# keyboard_main.net
KiCad netlist of a schematic drawn in Altium Designer
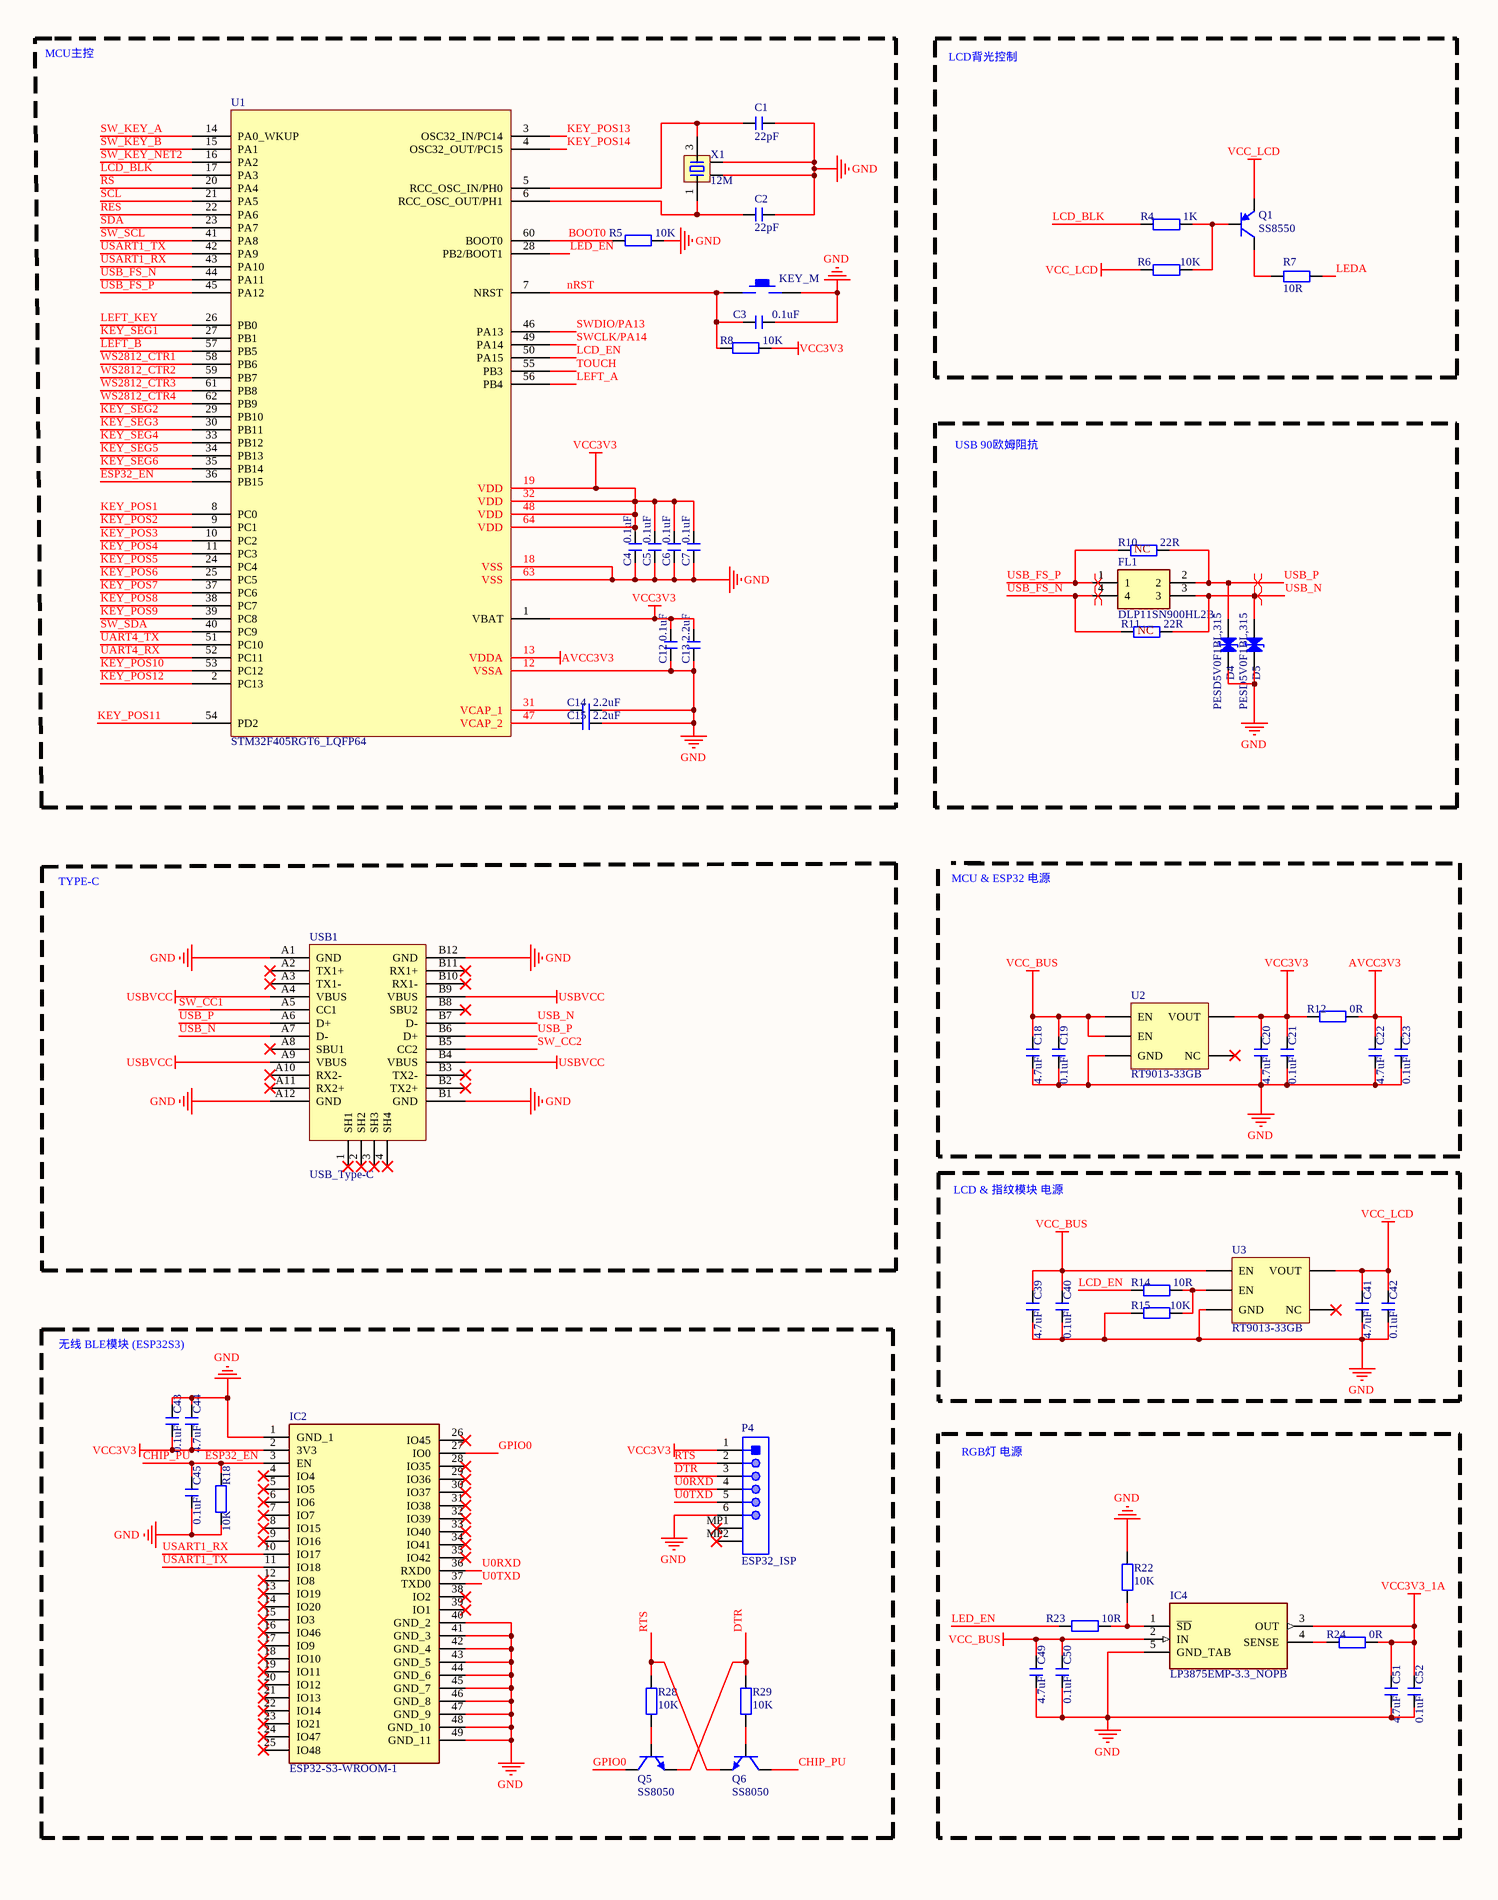
[diagram p0: keyboard_main.SchDoc, left]
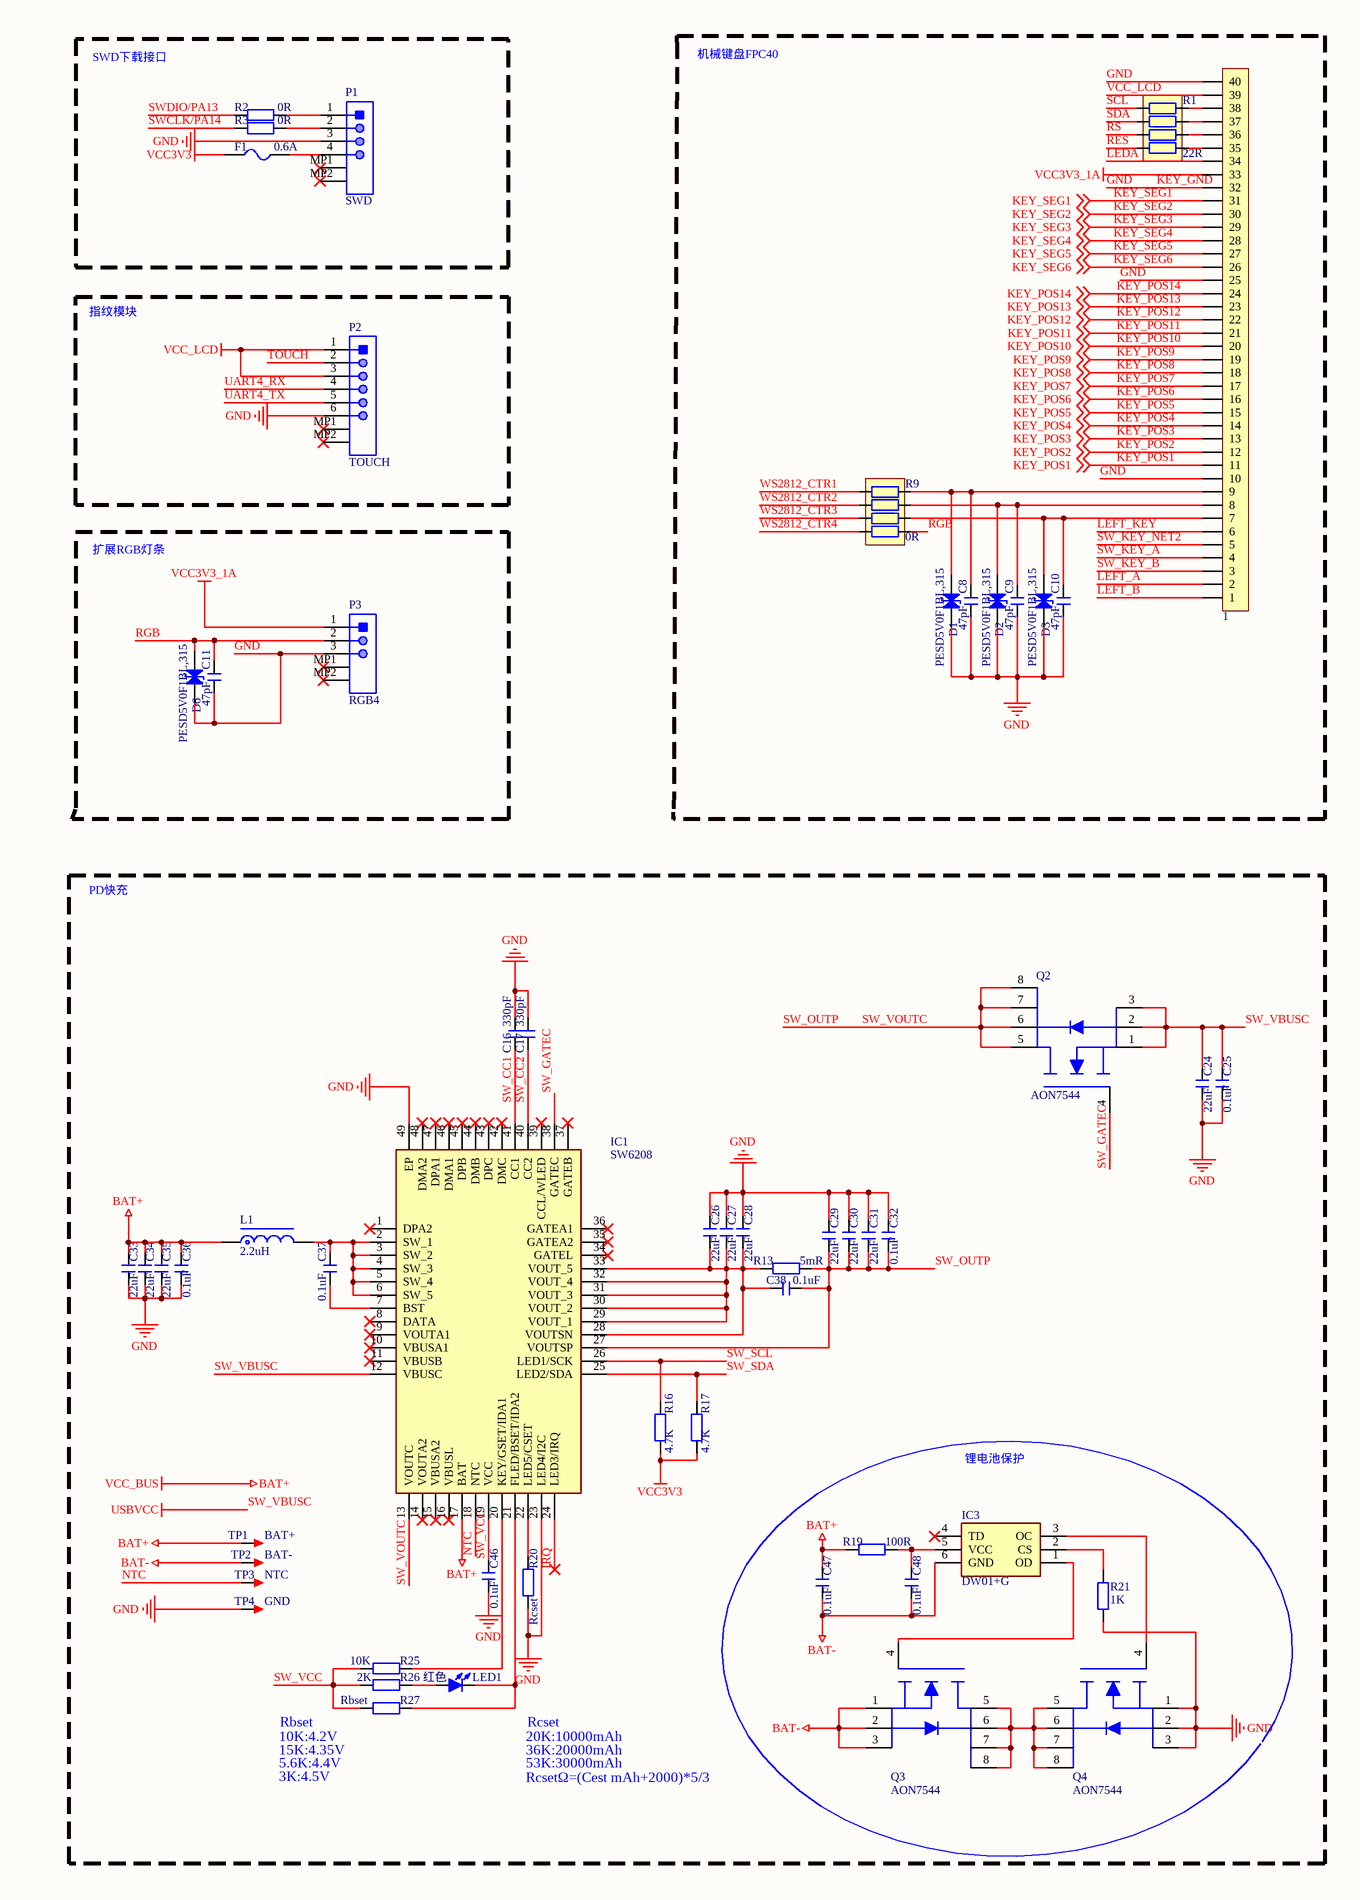
[diagram p1: keyboard_main.SchDoc, right]

(export (version "E")
  (design (tool "Eeschema 10.0.6"))
  (components
    (comp (ref "1")
      (value "FPC1.0-40P")
      (footprint "FPC0.5 2H-WS-40P")
      (description "FPC连接器")
      (fields (field (name "版权归属") "黎明电子style"))
      (libsource (lib "FPC连接器") (part "FPC-40P"))
    )
    (comp (ref "C1")
      (value "22pF")
      (footprint "C 0402_L")
      (description "贴片电容")
      (libsource (lib "0.1 - 电阻-电容-电感") (part "C"))
    )
    (comp (ref "C2")
      (value "22pF")
      (footprint "C 0402_L")
      (description "贴片电容")
      (libsource (lib "0.1 - 电阻-电容-电感") (part "C"))
    )
    (comp (ref "C3")
      (value "0.1uF")
      (footprint "C 0402_L")
      (description "贴片电容")
      (libsource (lib "0.1 - 电阻-电容-电感") (part "C"))
    )
    (comp (ref "C4")
      (value "0.1uF")
      (footprint "C 0402_L")
      (description "贴片电容")
      (libsource (lib "0.1 - 电阻-电容-电感") (part "C"))
    )
    (comp (ref "C5")
      (value "0.1uF")
      (footprint "C 0402_L")
      (description "贴片电容")
      (libsource (lib "0.1 - 电阻-电容-电感") (part "C"))
    )
    (comp (ref "C6")
      (value "0.1uF")
      (footprint "C 0402_L")
      (description "贴片电容")
      (libsource (lib "0.1 - 电阻-电容-电感") (part "C"))
    )
    (comp (ref "C7")
      (value "0.1uF")
      (footprint "C 0402_L")
      (description "贴片电容")
      (libsource (lib "0.1 - 电阻-电容-电感") (part "C"))
    )
    (comp (ref "C8")
      (value "47pF")
      (footprint "C 0402_L")
      (description "贴片电容")
      (libsource (lib "0.1 - 电阻-电容-电感") (part "C"))
    )
    (comp (ref "C9")
      (value "47pF")
      (footprint "C 0402_L")
      (description "贴片电容")
      (libsource (lib "0.1 - 电阻-电容-电感") (part "C"))
    )
    (comp (ref "C10")
      (value "47pF")
      (footprint "C 0402_L")
      (description "贴片电容")
      (libsource (lib "0.1 - 电阻-电容-电感") (part "C"))
    )
    (comp (ref "C11")
      (value "47pF")
      (footprint "C 0402_L")
      (description "贴片电容")
      (libsource (lib "0.1 - 电阻-电容-电感") (part "C"))
    )
    (comp (ref "C12")
      (value "0.1uF")
      (footprint "C 0402_L")
      (description "贴片电容")
      (libsource (lib "0.1 - 电阻-电容-电感") (part "C"))
    )
    (comp (ref "C13")
      (value "2.2uF")
      (footprint "C 0402_L")
      (description "贴片电容")
      (libsource (lib "0.1 - 电阻-电容-电感") (part "C"))
    )
    (comp (ref "C14")
      (value "2.2uF")
      (footprint "C 0402_L")
      (description "贴片电容")
      (libsource (lib "0.1 - 电阻-电容-电感") (part "C"))
    )
    (comp (ref "C15")
      (value "2.2uF")
      (footprint "C 0402_L")
      (description "贴片电容")
      (libsource (lib "0.1 - 电阻-电容-电感") (part "C"))
    )
    (comp (ref "C16")
      (value "330pF")
      (footprint "C 0402_L")
      (description "贴片电容")
      (libsource (lib "0.1 - 电阻-电容-电感") (part "C"))
    )
    (comp (ref "C17")
      (value "330pF")
      (footprint "C 0402_L")
      (description "贴片电容")
      (libsource (lib "0.1 - 电阻-电容-电感") (part "C"))
    )
    (comp (ref "C18")
      (value "4.7uF")
      (footprint "C 0402_L")
      (description "贴片电容")
      (libsource (lib "0.1 - 电阻-电容-电感") (part "C"))
    )
    (comp (ref "C19")
      (value "0.1uF")
      (footprint "C 0402_L")
      (description "贴片电容")
      (libsource (lib "0.1 - 电阻-电容-电感") (part "C"))
    )
    (comp (ref "C20")
      (value "4.7uF")
      (footprint "C 0402_L")
      (description "贴片电容")
      (libsource (lib "0.1 - 电阻-电容-电感") (part "C"))
    )
    (comp (ref "C21")
      (value "0.1uF")
      (footprint "C 0402_L")
      (description "贴片电容")
      (libsource (lib "0.1 - 电阻-电容-电感") (part "C"))
    )
    (comp (ref "C22")
      (value "4.7uF")
      (footprint "C 0402_L")
      (description "贴片电容")
      (libsource (lib "0.1 - 电阻-电容-电感") (part "C"))
    )
    (comp (ref "C23")
      (value "0.1uF")
      (footprint "C 0402_L")
      (description "贴片电容")
      (libsource (lib "0.1 - 电阻-电容-电感") (part "C"))
    )
    (comp (ref "C24")
      (value "22uF")
      (footprint "C 0805_L")
      (description "贴片电容")
      (libsource (lib "0.1 - 电阻-电容-电感") (part "C"))
    )
    (comp (ref "C25")
      (value "0.1uF")
      (footprint "C 0805_L")
      (description "贴片电容")
      (libsource (lib "0.1 - 电阻-电容-电感") (part "C"))
    )
    (comp (ref "C26")
      (value "22uF")
      (footprint "C 0805_L")
      (description "贴片电容")
      (libsource (lib "0.1 - 电阻-电容-电感") (part "C"))
    )
    (comp (ref "C27")
      (value "22uF")
      (footprint "C 0805_L")
      (description "贴片电容")
      (libsource (lib "0.1 - 电阻-电容-电感") (part "C"))
    )
    (comp (ref "C28")
      (value "22uF")
      (footprint "C 0805_L")
      (description "贴片电容")
      (libsource (lib "0.1 - 电阻-电容-电感") (part "C"))
    )
    (comp (ref "C29")
      (value "22uF")
      (footprint "C 0805_L")
      (description "贴片电容")
      (libsource (lib "0.1 - 电阻-电容-电感") (part "C"))
    )
    (comp (ref "C30")
      (value "22uF")
      (footprint "C 0805_L")
      (description "贴片电容")
      (libsource (lib "0.1 - 电阻-电容-电感") (part "C"))
    )
    (comp (ref "C31")
      (value "22uF")
      (footprint "C 0805_L")
      (description "贴片电容")
      (libsource (lib "0.1 - 电阻-电容-电感") (part "C"))
    )
    (comp (ref "C32")
      (value "0.1uF")
      (footprint "C 0805_L")
      (description "贴片电容")
      (libsource (lib "0.1 - 电阻-电容-电感") (part "C"))
    )
    (comp (ref "C33")
      (value "22uF")
      (footprint "C 0805_L")
      (description "贴片电容")
      (libsource (lib "0.1 - 电阻-电容-电感") (part "C"))
    )
    (comp (ref "C34")
      (value "22uF")
      (footprint "C 0805_L")
      (description "贴片电容")
      (libsource (lib "0.1 - 电阻-电容-电感") (part "C"))
    )
    (comp (ref "C35")
      (value "22uF")
      (footprint "C 0805_L")
      (description "贴片电容")
      (libsource (lib "0.1 - 电阻-电容-电感") (part "C"))
    )
    (comp (ref "C36")
      (value "0.1uF")
      (footprint "C 0805_L")
      (description "贴片电容")
      (libsource (lib "0.1 - 电阻-电容-电感") (part "C"))
    )
    (comp (ref "C37")
      (value "0.1uF")
      (footprint "C 0805_L")
      (description "贴片电容")
      (libsource (lib "0.1 - 电阻-电容-电感") (part "C"))
    )
    (comp (ref "C38")
      (value "0.1uF")
      (footprint "C 0805_L")
      (description "贴片电容")
      (libsource (lib "0.1 - 电阻-电容-电感") (part "C"))
    )
    (comp (ref "C39")
      (value "4.7uF")
      (footprint "C 0402_L")
      (description "贴片电容")
      (libsource (lib "0.1 - 电阻-电容-电感") (part "C"))
    )
    (comp (ref "C40")
      (value "0.1uF")
      (footprint "C 0402_L")
      (description "贴片电容")
      (libsource (lib "0.1 - 电阻-电容-电感") (part "C"))
    )
    (comp (ref "C41")
      (value "4.7uF")
      (footprint "C 0402_L")
      (description "贴片电容")
      (libsource (lib "0.1 - 电阻-电容-电感") (part "C"))
    )
    (comp (ref "C42")
      (value "0.1uF")
      (footprint "C 0402_L")
      (description "贴片电容")
      (libsource (lib "0.1 - 电阻-电容-电感") (part "C"))
    )
    (comp (ref "C43")
      (value "0.1uF")
      (footprint "C 0402_L")
      (description "贴片电容")
      (libsource (lib "0.1 - 电阻-电容-电感") (part "C"))
    )
    (comp (ref "C44")
      (value "4.7uF")
      (footprint "C 0402_L")
      (description "贴片电容")
      (libsource (lib "0.1 - 电阻-电容-电感") (part "C"))
    )
    (comp (ref "C45")
      (value "0.1uF")
      (footprint "C 0402_L")
      (description "贴片电容")
      (libsource (lib "0.1 - 电阻-电容-电感") (part "C"))
    )
    (comp (ref "C46")
      (value "0.1uF")
      (footprint "C 0402_L")
      (description "贴片电容")
      (libsource (lib "0.1 - 电阻-电容-电感") (part "C"))
    )
    (comp (ref "C47")
      (value "0.1uF")
      (footprint "C 0805_L")
      (description "贴片电容")
      (libsource (lib "0.1 - 电阻-电容-电感") (part "C"))
    )
    (comp (ref "C48")
      (value "0.1uF")
      (footprint "C 0805_L")
      (description "贴片电容")
      (libsource (lib "0.1 - 电阻-电容-电感") (part "C"))
    )
    (comp (ref "C49")
      (value "4.7uF")
      (footprint "C 0402_L")
      (description "贴片电容")
      (libsource (lib "0.1 - 电阻-电容-电感") (part "C"))
    )
    (comp (ref "C50")
      (value "0.1uF")
      (footprint "C 0402_L")
      (description "贴片电容")
      (libsource (lib "0.1 - 电阻-电容-电感") (part "C"))
    )
    (comp (ref "C51")
      (value "4.7uF")
      (footprint "C 0402_L")
      (description "贴片电容")
      (libsource (lib "0.1 - 电阻-电容-电感") (part "C"))
    )
    (comp (ref "C52")
      (value "0.1uF")
      (footprint "C 0402_L")
      (description "贴片电容")
      (libsource (lib "0.1 - 电阻-电容-电感") (part "C"))
    )
    (comp (ref "D1")
      (value "PESD5V0F1BL,315")
      (footprint "SOD-882_L1.0-W0.6-BI")
      (description "PESD5V0F1BL,315、ESD二极管、5.5V")
      (libsource (lib "0.2 -  二极管-整流桥") (part "PESD5V0F1BL,315"))
    )
    (comp (ref "D2")
      (value "PESD5V0F1BL,315")
      (footprint "SOD-882_L1.0-W0.6-BI")
      (description "PESD5V0F1BL,315、ESD二极管、5.5V")
      (libsource (lib "0.2 -  二极管-整流桥") (part "PESD5V0F1BL,315"))
    )
    (comp (ref "D3")
      (value "PESD5V0F1BL,315")
      (footprint "SOD-882_L1.0-W0.6-BI")
      (description "PESD5V0F1BL,315、ESD二极管、5.5V")
      (libsource (lib "0.2 -  二极管-整流桥") (part "PESD5V0F1BL,315"))
    )
    (comp (ref "D4")
      (value "PESD5V0F1BL,315")
      (footprint "SOD-882_L1.0-W0.6-BI")
      (description "PESD5V0F1BL,315、ESD二极管、5.5V")
      (libsource (lib "0.2 -  二极管-整流桥") (part "PESD5V0F1BL,315"))
    )
    (comp (ref "D5")
      (value "PESD5V0F1BL,315")
      (footprint "SOD-882_L1.0-W0.6-BI")
      (description "PESD5V0F1BL,315、ESD二极管、5.5V")
      (libsource (lib "0.2 -  二极管-整流桥") (part "PESD5V0F1BL,315"))
    )
    (comp (ref "D6")
      (value "PESD5V0F1BL,315")
      (footprint "SOD-882_L1.0-W0.6-BI")
      (description "PESD5V0F1BL,315、ESD二极管、5.5V")
      (libsource (lib "0.2 -  二极管-整流桥") (part "PESD5V0F1BL,315"))
    )
    (comp (ref "F1")
      (value "0.6A")
      (footprint "FU 0402")
      (description "贴片保险丝")
      (libsource (lib "2.0 - 保险丝-晶振-光耦") (part "FU"))
    )
    (comp (ref "FL1")
      (value "DLP11SN900HL2B")
      (footprint "vSeasky:DLP11SA350HL2B")
      (description "Filter")
      (fields (field (name "MOUSER PART NUMBER") "81-DLP11SN900HL2B"))
      (libsource (lib "vSeasky") (part "DLP11SN900HL2B"))
    )
    (comp (ref "IC1")
      (value "SW6208")
      (footprint "vSeasky:QFN40P600X600X80-49N")
      (description "Integrated Circuit")
      (libsource (lib "*") (part "SW6208"))
    )
    (comp (ref "IC2")
      (value "ESP32-S3-WROOM-1")
      (footprint "mx_pcb_library:ESP32S3WROOM1")
      (description "Integrated Circuit")
      (libsource (lib "mx_pcb_library") (part "ESP32-S3-WROOM-1"))
    )
    (comp (ref "IC3")
      (value "DW01+G")
      (footprint "vSeasky:SOT95P280X145-6N")
      (description "Integrated Circuit")
      (libsource (lib "*") (part "DW01+G"))
    )
    (comp (ref "IC4")
      (value "LP3875EMP-3.3_NOPB")
      (footprint "mx_pcb_library:SOT150P700X180-5N")
      (description "Integrated Circuit")
      (fields
        (field (name "MANUFACTURER_PART_NUMBER") "LP3875EMP-3.3/NOPB")
        (field (name "MOUSER PART NUMBER") "926-LP3875EMP33NOPB")
      )
      (libsource (lib "mx_pcb_library") (part "LP3875EMP-3.3_NOPB"))
    )
    (comp (ref "L1")
      (value "2.2uH")
      (footprint "CD42")
      (description "CD系列贴片线绕功率电感")
      (libsource (lib "0.1 - 电阻-电容-电感") (part "L-SMD"))
    )
    (comp (ref "LED1")
      (value "红色")
      (footprint "LED 0805G")
      (description "贴片LED")
      (libsource (lib "0.3 - LED发光二极管") (part "LED-SMD"))
    )
    (comp (ref "P1")
      (value "SWD")
      (footprint "JST-SM04B-SRSS-TB_V")
      (description "Male Header, Pitch 1 mm, 1 x 4 Position, Height 2.9 mm, -25 to 85 degC, RoHS, Tape and Reel")
      (fields (field (name "MANUFACTURER") "JST"))
      (libsource (lib "JST SH Connector") (part "SM04B-SRSS-TB(LF)(SN)"))
    )
    (comp (ref "P2")
      (value "TOUCH")
      (footprint "JST-SM06B-SRSS-TB_V")
      (description "Male Header, Pitch 1 mm, 1 x 6 Position, Height 2.9 mm, -25 to 85 degC, RoHS, Tape and Reel")
      (fields (field (name "MANUFACTURER") "JST"))
      (libsource (lib "JST SH Connector") (part "SM06B-SRSS-TB(LF)(SN)"))
    )
    (comp (ref "P3")
      (value "RGB4")
      (footprint "JST-SM03B-SRSS-TB_V")
      (description "Male Header, Pitch 1 mm, 1 x 3 Position, Height 2.9 mm, -25 to 85 degC, RoHS, Tape and Reel")
      (fields (field (name "MANUFACTURER") "JST"))
      (libsource (lib "JST SH Connector") (part "SM03B-SRSS-TB(LF)(SN)"))
    )
    (comp (ref "P4")
      (value "ESP32_ISP")
      (footprint "JST-SM06B-SRSS-TB_V")
      (description "Male Header, Pitch 1 mm, 1 x 6 Position, Height 2.9 mm, -25 to 85 degC, RoHS, Tape and Reel")
      (fields (field (name "MANUFACTURER") "JST"))
      (libsource (lib "JST SH Connector") (part "SM06B-SRSS-TB(LF)(SN)"))
    )
    (comp (ref "Q1")
      (value "SS8550")
      (footprint "SOT23-3N")
      (description "高频放大-PNP型")
      (libsource (lib "0.4 - 三极管") (part "8550-SMD"))
    )
    (comp (ref "Q2")
      (value "AON7544")
      (footprint "DFN-8_L3.0-W3.0-P0.65-BL")
      (libsource (lib "mx_pcb_library") (part "BSC070N10NS3GATMA1"))
    )
    (comp (ref "Q3")
      (value "AON7544")
      (footprint "DFN-8_L3.0-W3.0-P0.65-BL")
      (libsource (lib "mx_pcb_library") (part "BSC070N10NS3GATMA1"))
    )
    (comp (ref "Q4")
      (value "AON7544")
      (footprint "DFN-8_L3.0-W3.0-P0.65-BL")
      (libsource (lib "mx_pcb_library") (part "BSC070N10NS3GATMA1"))
    )
    (comp (ref "Q5")
      (value "SS8050")
      (footprint "SOT23-3N")
      (description "高频放大-NPN型")
      (libsource (lib "0.4 - 三极管") (part "8050-SMD"))
    )
    (comp (ref "Q6")
      (value "SS8050")
      (footprint "SOT23-3N")
      (description "高频放大-NPN型")
      (libsource (lib "0.4 - 三极管") (part "8050-SMD"))
    )
    (comp (ref "R1")
      (value "22R")
      (footprint "RCA-8P4R-0402")
      (description "贴片排阻")
      (libsource (lib "0.1 - 电阻-电容-电感") (part "R-8P4R"))
    )
    (comp (ref "R2")
      (value "0R")
      (footprint "R 0402_L")
      (description "贴片电阻")
      (libsource (lib "0.1 - 电阻-电容-电感") (part "R"))
    )
    (comp (ref "R3")
      (value "0R")
      (footprint "R 0402_L")
      (description "贴片电阻")
      (libsource (lib "0.1 - 电阻-电容-电感") (part "R"))
    )
    (comp (ref "R4")
      (value "1K")
      (footprint "R 0402_L")
      (description "贴片电阻")
      (libsource (lib "0.1 - 电阻-电容-电感") (part "R"))
    )
    (comp (ref "R5")
      (value "10K")
      (footprint "R 0402_L")
      (description "贴片电阻")
      (libsource (lib "0.1 - 电阻-电容-电感") (part "R"))
    )
    (comp (ref "R6")
      (value "10K")
      (footprint "R 0402_L")
      (description "贴片电阻")
      (libsource (lib "0.1 - 电阻-电容-电感") (part "R"))
    )
    (comp (ref "R7")
      (value "10R")
      (footprint "R 0402_L")
      (description "贴片电阻")
      (libsource (lib "0.1 - 电阻-电容-电感") (part "R"))
    )
    (comp (ref "R8")
      (value "10K")
      (footprint "R 0402_L")
      (description "贴片电阻")
      (libsource (lib "0.1 - 电阻-电容-电感") (part "R"))
    )
    (comp (ref "R9")
      (value "0R")
      (footprint "RCA-8P4R-0402")
      (description "贴片排阻")
      (libsource (lib "0.1 - 电阻-电容-电感") (part "R-8P4R"))
    )
    (comp (ref "R10")
      (value "22R")
      (footprint "R 0402_L")
      (description "贴片电阻")
      (libsource (lib "0.1 - 电阻-电容-电感") (part "R"))
    )
    (comp (ref "R11")
      (value "22R")
      (footprint "R 0402_L")
      (description "贴片电阻")
      (libsource (lib "0.1 - 电阻-电容-电感") (part "R"))
    )
    (comp (ref "R12")
      (value "0R")
      (footprint "R 0402_L")
      (description "贴片电阻")
      (libsource (lib "0.1 - 电阻-电容-电感") (part "R"))
    )
    (comp (ref "R13")
      (value "5mR")
      (footprint "R 1206_L")
      (description "贴片电阻")
      (libsource (lib "0.1 - 电阻-电容-电感") (part "R"))
    )
    (comp (ref "R14")
      (value "10R")
      (footprint "R 0402_L")
      (description "贴片电阻")
      (libsource (lib "0.1 - 电阻-电容-电感") (part "R"))
    )
    (comp (ref "R15")
      (value "10K")
      (footprint "R 0402_L")
      (description "贴片电阻")
      (libsource (lib "0.1 - 电阻-电容-电感") (part "R"))
    )
    (comp (ref "R16")
      (value "4.7K")
      (footprint "R 0402_L")
      (description "贴片电阻")
      (libsource (lib "0.1 - 电阻-电容-电感") (part "R"))
    )
    (comp (ref "R17")
      (value "4.7K")
      (footprint "R 0402_L")
      (description "贴片电阻")
      (libsource (lib "0.1 - 电阻-电容-电感") (part "R"))
    )
    (comp (ref "R18")
      (value "10K")
      (footprint "R 0402_L")
      (description "贴片电阻")
      (libsource (lib "0.1 - 电阻-电容-电感") (part "R"))
    )
    (comp (ref "R19")
      (value "100R")
      (footprint "R 0402_L")
      (description "贴片电阻")
      (libsource (lib "0.1 - 电阻-电容-电感") (part "R"))
    )
    (comp (ref "R20")
      (value "Rcset")
      (footprint "R 0402_L")
      (description "贴片电阻")
      (libsource (lib "0.1 - 电阻-电容-电感") (part "R"))
    )
    (comp (ref "R21")
      (value "1K")
      (footprint "R 0402_L")
      (description "贴片电阻")
      (libsource (lib "0.1 - 电阻-电容-电感") (part "R"))
    )
    (comp (ref "R22")
      (value "10K")
      (footprint "R 0402_L")
      (description "贴片电阻")
      (libsource (lib "0.1 - 电阻-电容-电感") (part "R"))
    )
    (comp (ref "R23")
      (value "10R")
      (footprint "R 0402_L")
      (description "贴片电阻")
      (libsource (lib "0.1 - 电阻-电容-电感") (part "R"))
    )
    (comp (ref "R24")
      (value "0R")
      (footprint "R 0402_L")
      (description "贴片电阻")
      (libsource (lib "0.1 - 电阻-电容-电感") (part "R"))
    )
    (comp (ref "R25")
      (value "10K")
      (footprint "R 0402_L")
      (description "贴片电阻")
      (libsource (lib "0.1 - 电阻-电容-电感") (part "R"))
    )
    (comp (ref "R26")
      (value "2K")
      (footprint "R 0402_L")
      (description "贴片电阻")
      (libsource (lib "0.1 - 电阻-电容-电感") (part "R"))
    )
    (comp (ref "R27")
      (value "Rbset")
      (footprint "R 0402_L")
      (description "贴片电阻")
      (libsource (lib "0.1 - 电阻-电容-电感") (part "R"))
    )
    (comp (ref "R28")
      (value "10K")
      (footprint "R 0402_L")
      (description "贴片电阻")
      (libsource (lib "0.1 - 电阻-电容-电感") (part "R"))
    )
    (comp (ref "R29")
      (value "10K")
      (footprint "R 0402_L")
      (description "贴片电阻")
      (libsource (lib "0.1 - 电阻-电容-电感") (part "R"))
    )
    (comp (ref "RST1")
      (value "KEY_M")
      (footprint "SMD-3.2*4.2")
      (libsource (lib "mx_pcb_library") (part "KEY_M"))
    )
    (comp (ref "TP1")
      (value "BAT+")
      (footprint "TEST 1.6")
      (description "测试点")
      (libsource (lib "4.1 - 未分类器件") (part "TEST"))
    )
    (comp (ref "TP2")
      (value "BAT-")
      (footprint "TEST 1.6")
      (description "测试点")
      (libsource (lib "4.1 - 未分类器件") (part "TEST"))
    )
    (comp (ref "TP3")
      (value "NTC")
      (footprint "TEST 1.6")
      (description "测试点")
      (libsource (lib "4.1 - 未分类器件") (part "TEST"))
    )
    (comp (ref "TP4")
      (value "GND")
      (footprint "TEST 1.6")
      (description "测试点")
      (libsource (lib "4.1 - 未分类器件") (part "TEST"))
    )
    (comp (ref "U1")
      (value "STM32F405RGT6_LQFP64")
      (footprint "LQFP-64_10X10X05P")
      (libsource (lib "mx_pcb_library") (part "STM32F405RGT6_LQFP64"))
    )
    (comp (ref "U2")
      (value "RT9013-33GB")
      (footprint "SOT23-5M")
      (libsource (lib "mx_pcb_library") (part "RT9013-33GB"))
    )
    (comp (ref "U3")
      (value "RT9013-33GB")
      (footprint "SOT23-5M")
      (libsource (lib "mx_pcb_library") (part "RT9013-33GB"))
    )
    (comp (ref "USB1")
      (value "USB_Type-C")
      (footprint "Type-C-TOP")
      (libsource (lib "mx_pcb_library") (part "USB_Type-C"))
    )
    (comp (ref "X1")
      (value "12M")
      (footprint "OSC 3225-4P")
      (description "4脚无源晶振")
      (libsource (lib "2.0 - 保险丝-晶振-光耦") (part "XTAL-4P"))
    )
  )
  (nets
    (net (code "1") (name "/BOOT0") (class "Default")
      (node (ref "R5") (pin "1") (pinfunction "1_1") (pintype "passive"))
      (node (ref "U1") (pin "60") (pinfunction "BOOT0_60") (pintype "passive"))
    )
    (net (code "2") (name "/CHIP_PU") (class "Default")
      (node (ref "C45") (pin "1") (pinfunction "1_1") (pintype "passive"))
      (node (ref "IC2") (pin "3") (pinfunction "EN_3") (pintype "passive"))
      (node (ref "Q6") (pin "3") (pinfunction "C_3") (pintype "passive"))
      (node (ref "R18") (pin "1") (pinfunction "1_1") (pintype "passive"))
      (node (ref "U1") (pin "36") (pinfunction "PB15_36") (pintype "passive"))
    )
    (net (code "3") (name "/DTR") (class "Default")
      (node (ref "P4") (pin "3") (pinfunction "3_3") (pintype "passive"))
      (node (ref "Q5") (pin "2") (pinfunction "E_2") (pintype "passive"))
      (node (ref "R29") (pin "1") (pinfunction "1_1") (pintype "passive"))
    )
    (net (code "4") (name "/GPIO0") (class "Default")
      (node (ref "IC2") (pin "27") (pinfunction "IO0_27") (pintype "passive"))
      (node (ref "Q5") (pin "3") (pinfunction "C_3") (pintype "passive"))
    )
    (net (code "5") (name "/IRQ") (class "Default")
      (node (ref "IC1") (pin "24") (pinfunction "LED3/IRQ_24") (pintype "passive+no_connect"))
    )
    (net (code "6") (name "/LCD_BLK") (class "Default")
      (node (ref "R4") (pin "1") (pinfunction "1_1") (pintype "passive"))
      (node (ref "U1") (pin "17") (pinfunction "PA3_17") (pintype "passive"))
    )
    (net (code "7") (name "/LCD_EN") (class "Default")
      (node (ref "R14") (pin "1") (pinfunction "1_1") (pintype "passive"))
      (node (ref "U1") (pin "50") (pinfunction "PA15_50") (pintype "passive"))
    )
    (net (code "8") (name "/LEDA") (class "Default")
      (node (ref "1") (pin "34") (pinfunction "34_34") (pintype "passive"))
      (node (ref "R7") (pin "1") (pinfunction "1_1") (pintype "passive"))
    )
    (net (code "9") (name "/LED_EN") (class "Default")
      (node (ref "R23") (pin "1") (pinfunction "1_1") (pintype "passive"))
      (node (ref "U1") (pin "28") (pinfunction "PB2/BOOT1_28") (pintype "passive"))
    )
    (net (code "10") (name "/LEFT_A") (class "Default")
      (node (ref "1") (pin "2") (pinfunction "2_2") (pintype "passive"))
      (node (ref "U1") (pin "56") (pinfunction "PB4_56") (pintype "passive"))
    )
    (net (code "11") (name "/LEFT_B") (class "Default")
      (node (ref "1") (pin "1") (pinfunction "1_1") (pintype "passive"))
      (node (ref "U1") (pin "57") (pinfunction "PB5_57") (pintype "passive"))
    )
    (net (code "12") (name "/LEFT_KEY") (class "Default")
      (node (ref "1") (pin "6") (pinfunction "6_6") (pintype "passive"))
      (node (ref "U1") (pin "26") (pinfunction "PB0_26") (pintype "passive"))
    )
    (net (code "13") (name "/NTC") (class "Default")
      (node (ref "IC1") (pin "18") (pinfunction "NTC_18") (pintype "passive"))
      (node (ref "TP3") (pin "1") (pinfunction "1_1") (pintype "passive"))
    )
    (net (code "14") (name "/RES") (class "Default")
      (node (ref "R1") (pin "4") (pinfunction "4_4") (pintype "passive"))
      (node (ref "U1") (pin "22") (pinfunction "PA6_22") (pintype "passive"))
    )
    (net (code "15") (name "/RGB") (class "Default")
      (node (ref "C11") (pin "2") (pinfunction "2_2") (pintype "passive"))
      (node (ref "D6") (pin "1") (pinfunction "A_1") (pintype "passive"))
      (node (ref "P3") (pin "2") (pinfunction "2_2") (pintype "passive"))
      (node (ref "R9") (pin "5") (pinfunction "5_5") (pintype "passive"))
    )
    (net (code "16") (name "/RS") (class "Default")
      (node (ref "R1") (pin "3") (pinfunction "3_3") (pintype "passive"))
      (node (ref "U1") (pin "20") (pinfunction "PA4_20") (pintype "passive"))
    )
    (net (code "17") (name "/RTS") (class "Default")
      (node (ref "P4") (pin "2") (pinfunction "2_2") (pintype "passive"))
      (node (ref "Q6") (pin "2") (pinfunction "E_2") (pintype "passive"))
      (node (ref "R28") (pin "1") (pinfunction "1_1") (pintype "passive"))
    )
    (net (code "18") (name "/SCL") (class "Default")
      (node (ref "R1") (pin "1") (pinfunction "1_1") (pintype "passive"))
      (node (ref "U1") (pin "21") (pinfunction "PA5_21") (pintype "passive"))
    )
    (net (code "19") (name "/SDA") (class "Default")
      (node (ref "R1") (pin "2") (pinfunction "2_2") (pintype "passive"))
      (node (ref "U1") (pin "23") (pinfunction "PA7_23") (pintype "passive"))
    )
    (net (code "20") (name "/SWCLK{slash}PA14") (class "Default")
      (node (ref "R3") (pin "1") (pinfunction "1_1") (pintype "passive"))
      (node (ref "U1") (pin "49") (pinfunction "PA14_49") (pintype "passive"))
    )
    (net (code "21") (name "/SWDIO{slash}PA13") (class "Default")
      (node (ref "R2") (pin "1") (pinfunction "1_1") (pintype "passive"))
      (node (ref "U1") (pin "46") (pinfunction "PA13_46") (pintype "passive"))
    )
    (net (code "22") (name "/SW_CC1") (class "Default")
      (node (ref "C16") (pin "1") (pinfunction "1_1") (pintype "passive"))
      (node (ref "IC1") (pin "41") (pinfunction "CC1_41") (pintype "passive"))
      (node (ref "USB1") (pin "A5") (pinfunction "CC1_A5") (pintype "passive"))
    )
    (net (code "23") (name "/SW_CC2") (class "Default")
      (node (ref "C17") (pin "1") (pinfunction "1_1") (pintype "passive"))
      (node (ref "IC1") (pin "40") (pinfunction "CC2_40") (pintype "passive"))
      (node (ref "USB1") (pin "B5") (pinfunction "CC2_B5") (pintype "passive"))
    )
    (net (code "24") (name "/SW_GATEC") (class "Default")
      (node (ref "IC1") (pin "38") (pinfunction "GATEC_38") (pintype "passive"))
      (node (ref "Q2") (pin "4") (pinfunction "4_4") (pintype "passive"))
    )
    (net (code "25") (name "/SW_KEY_A") (class "Default")
      (node (ref "1") (pin "4") (pinfunction "4_4") (pintype "passive"))
      (node (ref "U1") (pin "14") (pinfunction "PA0_WKUP_14") (pintype "passive"))
    )
    (net (code "26") (name "/SW_KEY_B") (class "Default")
      (node (ref "1") (pin "3") (pinfunction "3_3") (pintype "passive"))
      (node (ref "U1") (pin "15") (pinfunction "PA1_15") (pintype "passive"))
    )
    (net (code "27") (name "/SW_KEY_NET2") (class "Default")
      (node (ref "1") (pin "5") (pinfunction "5_5") (pintype "passive"))
      (node (ref "U1") (pin "16") (pinfunction "PA2_16") (pintype "passive"))
    )
    (net (code "28") (name "/SW_OUTP") (class "Default")
      (node (ref "C29") (pin "1") (pinfunction "1_1") (pintype "passive"))
      (node (ref "C30") (pin "1") (pinfunction "1_1") (pintype "passive"))
      (node (ref "C31") (pin "1") (pinfunction "1_1") (pintype "passive"))
      (node (ref "C32") (pin "1") (pinfunction "1_1") (pintype "passive"))
      (node (ref "C38") (pin "2") (pinfunction "2_2") (pintype "passive"))
      (node (ref "IC1") (pin "13") (pinfunction "VOUTC_13") (pintype "passive"))
      (node (ref "IC1") (pin "27") (pinfunction "VOUTSP_27") (pintype "passive"))
      (node (ref "Q2") (pin "5") (pinfunction "5_5") (pintype "passive"))
      (node (ref "Q2") (pin "6") (pinfunction "6_6") (pintype "passive"))
      (node (ref "Q2") (pin "7") (pinfunction "7_7") (pintype "passive"))
      (node (ref "Q2") (pin "8") (pinfunction "8_8") (pintype "passive"))
      (node (ref "R13") (pin "2") (pinfunction "2_2") (pintype "passive"))
    )
    (net (code "29") (name "/SW_SCL") (class "Default")
      (node (ref "IC1") (pin "26") (pinfunction "LED1/SCK_26") (pintype "passive"))
      (node (ref "R16") (pin "2") (pinfunction "2_2") (pintype "passive"))
      (node (ref "U1") (pin "41") (pinfunction "PA8_41") (pintype "passive"))
    )
    (net (code "30") (name "/SW_SDA") (class "Default")
      (node (ref "IC1") (pin "25") (pinfunction "LED2/SDA_25") (pintype "passive"))
      (node (ref "R17") (pin "2") (pinfunction "2_2") (pintype "passive"))
      (node (ref "U1") (pin "40") (pinfunction "PC9_40") (pintype "passive"))
    )
    (net (code "31") (name "/SW_VCC") (class "Default")
      (node (ref "C46") (pin "2") (pinfunction "2_2") (pintype "passive"))
      (node (ref "IC1") (pin "19") (pinfunction "VCC_19") (pintype "passive"))
      (node (ref "R25") (pin "1") (pinfunction "1_1") (pintype "passive"))
      (node (ref "R26") (pin "1") (pinfunction "1_1") (pintype "passive"))
      (node (ref "R27") (pin "1") (pinfunction "1_1") (pintype "passive"))
    )
    (net (code "32") (name "/TOUCH") (class "Default")
      (node (ref "P2") (pin "2") (pinfunction "2_2") (pintype "passive"))
      (node (ref "U1") (pin "55") (pinfunction "PB3_55") (pintype "passive"))
    )
    (net (code "33") (name "/U0RXD") (class "Default")
      (node (ref "IC2") (pin "36") (pinfunction "RXD0_36") (pintype "passive"))
      (node (ref "P4") (pin "4") (pinfunction "4_4") (pintype "passive"))
    )
    (net (code "34") (name "/U0TXD") (class "Default")
      (node (ref "IC2") (pin "37") (pinfunction "TXD0_37") (pintype "passive"))
      (node (ref "P4") (pin "5") (pinfunction "5_5") (pintype "passive"))
    )
    (net (code "35") (name "/UART4_RX") (class "Default")
      (node (ref "P2") (pin "4") (pinfunction "4_4") (pintype "passive"))
      (node (ref "U1") (pin "52") (pinfunction "PC11_52") (pintype "passive"))
    )
    (net (code "36") (name "/UART4_TX") (class "Default")
      (node (ref "P2") (pin "5") (pinfunction "5_5") (pintype "passive"))
      (node (ref "U1") (pin "51") (pinfunction "PC10_51") (pintype "passive"))
    )
    (net (code "37") (name "/USART1_RX") (class "Default")
      (node (ref "IC2") (pin "10") (pinfunction "IO17_10") (pintype "passive"))
      (node (ref "U1") (pin "43") (pinfunction "PA10_43") (pintype "passive"))
    )
    (net (code "38") (name "/USART1_TX") (class "Default")
      (node (ref "IC2") (pin "11") (pinfunction "IO18_11") (pintype "passive"))
      (node (ref "U1") (pin "42") (pinfunction "PA9_42") (pintype "passive"))
    )
    (net (code "39") (name "/USB_FS_N") (class "Default")
      (node (ref "FL1") (pin "4") (pinfunction "4_4") (pintype "passive"))
      (node (ref "R11") (pin "1") (pinfunction "1_1") (pintype "passive"))
      (node (ref "U1") (pin "44") (pinfunction "PA11_44") (pintype "passive"))
    )
    (net (code "40") (name "/USB_FS_P") (class "Default")
      (node (ref "FL1") (pin "1") (pinfunction "1_1") (pintype "passive"))
      (node (ref "R10") (pin "1") (pinfunction "1_1") (pintype "passive"))
      (node (ref "U1") (pin "45") (pinfunction "PA12_45") (pintype "passive"))
    )
    (net (code "41") (name "/USB_N") (class "Default")
      (node (ref "D5") (pin "1") (pinfunction "A_1") (pintype "passive"))
      (node (ref "FL1") (pin "3") (pinfunction "3_3") (pintype "passive"))
      (node (ref "R11") (pin "2") (pinfunction "2_2") (pintype "passive"))
      (node (ref "USB1") (pin "A7") (pinfunction "D-_A7") (pintype "passive"))
      (node (ref "USB1") (pin "B7") (pinfunction "D-_B7") (pintype "passive"))
    )
    (net (code "42") (name "/USB_P") (class "Default")
      (node (ref "D4") (pin "1") (pinfunction "A_1") (pintype "passive"))
      (node (ref "FL1") (pin "2") (pinfunction "2_2") (pintype "passive"))
      (node (ref "R10") (pin "2") (pinfunction "2_2") (pintype "passive"))
      (node (ref "USB1") (pin "A6") (pinfunction "D+_A6") (pintype "passive"))
      (node (ref "USB1") (pin "B6") (pinfunction "D+_B6") (pintype "passive"))
    )
    (net (code "43") (name "/WS2812_CTR1") (class "Default")
      (node (ref "R9") (pin "1") (pinfunction "1_1") (pintype "passive"))
      (node (ref "U1") (pin "58") (pinfunction "PB6_58") (pintype "passive"))
    )
    (net (code "44") (name "/WS2812_CTR2") (class "Default")
      (node (ref "R9") (pin "2") (pinfunction "2_2") (pintype "passive"))
      (node (ref "U1") (pin "59") (pinfunction "PB7_59") (pintype "passive"))
    )
    (net (code "45") (name "/WS2812_CTR3") (class "Default")
      (node (ref "R9") (pin "3") (pinfunction "3_3") (pintype "passive"))
      (node (ref "U1") (pin "61") (pinfunction "PB8_61") (pintype "passive"))
    )
    (net (code "46") (name "/WS2812_CTR4") (class "Default")
      (node (ref "R9") (pin "4") (pinfunction "4_4") (pintype "passive"))
      (node (ref "U1") (pin "62") (pinfunction "PB9_62") (pintype "passive"))
    )
    (net (code "47") (name "/nRST") (class "Default")
      (node (ref "C3") (pin "1") (pinfunction "1_1") (pintype "passive"))
      (node (ref "R8") (pin "1") (pinfunction "1_1") (pintype "passive"))
      (node (ref "RST1") (pin "1") (pinfunction "1_1") (pintype "passive"))
      (node (ref "U1") (pin "7") (pinfunction "NRST_7") (pintype "passive"))
    )
    (net (code "48") (name "AVCC3V3") (class "Default")
      (node (ref "C22") (pin "1") (pinfunction "1_1") (pintype "passive"))
      (node (ref "C23") (pin "1") (pinfunction "1_1") (pintype "passive"))
      (node (ref "R12") (pin "2") (pinfunction "2_2") (pintype "passive"))
      (node (ref "U1") (pin "13") (pinfunction "VDDA_13") (pintype "passive"))
    )
    (net (code "49") (name "BAT+") (class "Default")
      (node (ref "C18") (pin "1") (pinfunction "1_1") (pintype "passive"))
      (node (ref "C19") (pin "1") (pinfunction "1_1") (pintype "passive"))
      (node (ref "C33") (pin "2") (pinfunction "2_2") (pintype "passive"))
      (node (ref "C34") (pin "2") (pinfunction "2_2") (pintype "passive"))
      (node (ref "C35") (pin "2") (pinfunction "2_2") (pintype "passive"))
      (node (ref "C36") (pin "2") (pinfunction "2_2") (pintype "passive"))
      (node (ref "C39") (pin "1") (pinfunction "1_1") (pintype "passive"))
      (node (ref "C40") (pin "1") (pinfunction "1_1") (pintype "passive"))
      (node (ref "C47") (pin "1") (pinfunction "1_1") (pintype "passive"))
      (node (ref "C49") (pin "1") (pinfunction "1_1") (pintype "passive"))
      (node (ref "C50") (pin "1") (pinfunction "1_1") (pintype "passive"))
      (node (ref "IC1") (pin "17") (pinfunction "BAT_17") (pintype "passive"))
      (node (ref "IC4") (pin "2") (pinfunction "IN_2") (pintype "input"))
      (node (ref "L1") (pin "1") (pinfunction "1_1") (pintype "passive"))
      (node (ref "R19") (pin "2") (pinfunction "2_2") (pintype "passive"))
      (node (ref "TP1") (pin "1") (pinfunction "1_1") (pintype "passive"))
      (node (ref "U2") (pin "1") (pinfunction "EN_1") (pintype "passive"))
      (node (ref "U2") (pin "3") (pinfunction "EN_3") (pintype "passive"))
      (node (ref "U3") (pin "1") (pinfunction "EN_1") (pintype "passive"))
    )
    (net (code "50") (name "BAT-") (class "Default")
      (node (ref "C47") (pin "2") (pinfunction "2_2") (pintype "passive"))
      (node (ref "C48") (pin "2") (pinfunction "2_2") (pintype "passive"))
      (node (ref "IC3") (pin "6") (pinfunction "GND_6") (pintype "passive"))
      (node (ref "Q3") (pin "1") (pinfunction "1_1") (pintype "passive"))
      (node (ref "Q3") (pin "2") (pinfunction "2_2") (pintype "passive"))
      (node (ref "Q3") (pin "3") (pinfunction "3_3") (pintype "passive"))
      (node (ref "TP2") (pin "1") (pinfunction "1_1") (pintype "passive"))
    )
    (net (code "51") (name "GND") (class "Default")
      (node (ref "1") (pin "10") (pinfunction "10_10") (pintype "passive"))
      (node (ref "1") (pin "25") (pinfunction "25_25") (pintype "passive"))
      (node (ref "1") (pin "32") (pinfunction "32_32") (pintype "passive"))
      (node (ref "1") (pin "40") (pinfunction "40_40") (pintype "passive"))
      (node (ref "C1") (pin "2") (pinfunction "2_2") (pintype "passive"))
      (node (ref "C10") (pin "1") (pinfunction "1_1") (pintype "passive"))
      (node (ref "C11") (pin "1") (pinfunction "1_1") (pintype "passive"))
      (node (ref "C12") (pin "1") (pinfunction "1_1") (pintype "passive"))
      (node (ref "C13") (pin "1") (pinfunction "1_1") (pintype "passive"))
      (node (ref "C14") (pin "1") (pinfunction "1_1") (pintype "passive"))
      (node (ref "C15") (pin "1") (pinfunction "1_1") (pintype "passive"))
      (node (ref "C16") (pin "2") (pinfunction "2_2") (pintype "passive"))
      (node (ref "C17") (pin "2") (pinfunction "2_2") (pintype "passive"))
      (node (ref "C18") (pin "2") (pinfunction "2_2") (pintype "passive"))
      (node (ref "C19") (pin "2") (pinfunction "2_2") (pintype "passive"))
      (node (ref "C2") (pin "2") (pinfunction "2_2") (pintype "passive"))
      (node (ref "C20") (pin "2") (pinfunction "2_2") (pintype "passive"))
      (node (ref "C21") (pin "2") (pinfunction "2_2") (pintype "passive"))
      (node (ref "C22") (pin "2") (pinfunction "2_2") (pintype "passive"))
      (node (ref "C23") (pin "2") (pinfunction "2_2") (pintype "passive"))
      (node (ref "C24") (pin "1") (pinfunction "1_1") (pintype "passive"))
      (node (ref "C25") (pin "1") (pinfunction "1_1") (pintype "passive"))
      (node (ref "C26") (pin "2") (pinfunction "2_2") (pintype "passive"))
      (node (ref "C27") (pin "2") (pinfunction "2_2") (pintype "passive"))
      (node (ref "C28") (pin "2") (pinfunction "2_2") (pintype "passive"))
      (node (ref "C29") (pin "2") (pinfunction "2_2") (pintype "passive"))
      (node (ref "C3") (pin "2") (pinfunction "2_2") (pintype "passive"))
      (node (ref "C30") (pin "2") (pinfunction "2_2") (pintype "passive"))
      (node (ref "C31") (pin "2") (pinfunction "2_2") (pintype "passive"))
      (node (ref "C32") (pin "2") (pinfunction "2_2") (pintype "passive"))
      (node (ref "C33") (pin "1") (pinfunction "1_1") (pintype "passive"))
      (node (ref "C34") (pin "1") (pinfunction "1_1") (pintype "passive"))
      (node (ref "C35") (pin "1") (pinfunction "1_1") (pintype "passive"))
      (node (ref "C36") (pin "1") (pinfunction "1_1") (pintype "passive"))
      (node (ref "C39") (pin "2") (pinfunction "2_2") (pintype "passive"))
      (node (ref "C4") (pin "1") (pinfunction "1_1") (pintype "passive"))
      (node (ref "C40") (pin "2") (pinfunction "2_2") (pintype "passive"))
      (node (ref "C41") (pin "2") (pinfunction "2_2") (pintype "passive"))
      (node (ref "C42") (pin "2") (pinfunction "2_2") (pintype "passive"))
      (node (ref "C43") (pin "1") (pinfunction "1_1") (pintype "passive"))
      (node (ref "C44") (pin "1") (pinfunction "1_1") (pintype "passive"))
      (node (ref "C45") (pin "2") (pinfunction "2_2") (pintype "passive"))
      (node (ref "C46") (pin "1") (pinfunction "1_1") (pintype "passive"))
      (node (ref "C49") (pin "2") (pinfunction "2_2") (pintype "passive"))
      (node (ref "C5") (pin "1") (pinfunction "1_1") (pintype "passive"))
      (node (ref "C50") (pin "2") (pinfunction "2_2") (pintype "passive"))
      (node (ref "C51") (pin "2") (pinfunction "2_2") (pintype "passive"))
      (node (ref "C52") (pin "2") (pinfunction "2_2") (pintype "passive"))
      (node (ref "C6") (pin "1") (pinfunction "1_1") (pintype "passive"))
      (node (ref "C7") (pin "1") (pinfunction "1_1") (pintype "passive"))
      (node (ref "C8") (pin "1") (pinfunction "1_1") (pintype "passive"))
      (node (ref "C9") (pin "1") (pinfunction "1_1") (pintype "passive"))
      (node (ref "D1") (pin "2") (pinfunction "K_2") (pintype "passive"))
      (node (ref "D2") (pin "2") (pinfunction "K_2") (pintype "passive"))
      (node (ref "D3") (pin "2") (pinfunction "K_2") (pintype "passive"))
      (node (ref "D4") (pin "2") (pinfunction "K_2") (pintype "passive"))
      (node (ref "D5") (pin "2") (pinfunction "K_2") (pintype "passive"))
      (node (ref "D6") (pin "2") (pinfunction "K_2") (pintype "passive"))
      (node (ref "IC1") (pin "23") (pinfunction "LED4/I2C_23") (pintype "passive"))
      (node (ref "IC1") (pin "49") (pinfunction "EP_49") (pintype "passive"))
      (node (ref "IC2") (pin "1") (pinfunction "GND_1_1") (pintype "passive"))
      (node (ref "IC2") (pin "40") (pinfunction "GND_2_40") (pintype "passive"))
      (node (ref "IC2") (pin "41") (pinfunction "GND_3_41") (pintype "passive"))
      (node (ref "IC2") (pin "42") (pinfunction "GND_4_42") (pintype "passive"))
      (node (ref "IC2") (pin "43") (pinfunction "GND_5_43") (pintype "passive"))
      (node (ref "IC2") (pin "44") (pinfunction "GND_6_44") (pintype "passive"))
      (node (ref "IC2") (pin "45") (pinfunction "GND_7_45") (pintype "passive"))
      (node (ref "IC2") (pin "46") (pinfunction "GND_8_46") (pintype "passive"))
      (node (ref "IC2") (pin "47") (pinfunction "GND_9_47") (pintype "passive"))
      (node (ref "IC2") (pin "48") (pinfunction "GND_10_48") (pintype "passive"))
      (node (ref "IC2") (pin "49") (pinfunction "GND_11_49") (pintype "passive"))
      (node (ref "IC4") (pin "5") (pinfunction "GND_TAB_5") (pintype "power_in"))
      (node (ref "P1") (pin "3") (pinfunction "3_3") (pintype "passive"))
      (node (ref "P2") (pin "6") (pinfunction "6_6") (pintype "passive"))
      (node (ref "P3") (pin "3") (pinfunction "3_3") (pintype "passive"))
      (node (ref "P4") (pin "6") (pinfunction "6_6") (pintype "passive"))
      (node (ref "Q4") (pin "1") (pinfunction "1_1") (pintype "passive"))
      (node (ref "Q4") (pin "2") (pinfunction "2_2") (pintype "passive"))
      (node (ref "Q4") (pin "3") (pinfunction "3_3") (pintype "passive"))
      (node (ref "R15") (pin "2") (pinfunction "2_2") (pintype "passive"))
      (node (ref "R18") (pin "2") (pinfunction "2_2") (pintype "passive"))
      (node (ref "R20") (pin "2") (pinfunction "2_2") (pintype "passive"))
      (node (ref "R21") (pin "2") (pinfunction "2_2") (pintype "passive"))
      (node (ref "R22") (pin "1") (pinfunction "1_1") (pintype "passive"))
      (node (ref "R5") (pin "2") (pinfunction "2_2") (pintype "passive"))
      (node (ref "RST1") (pin "2") (pinfunction "2_2") (pintype "passive"))
      (node (ref "TP4") (pin "1") (pinfunction "1_1") (pintype "passive"))
      (node (ref "U1") (pin "12") (pinfunction "VSSA_12") (pintype "passive"))
      (node (ref "U1") (pin "18") (pinfunction "VSS_18") (pintype "passive"))
      (node (ref "U1") (pin "63") (pinfunction "VSS_63") (pintype "passive"))
      (node (ref "U2") (pin "2") (pinfunction "GND_2") (pintype "passive"))
      (node (ref "U3") (pin "2") (pinfunction "GND_2") (pintype "passive"))
      (node (ref "USB1") (pin "A1") (pinfunction "GND_A1") (pintype "passive"))
      (node (ref "USB1") (pin "A12") (pinfunction "GND_A12") (pintype "passive"))
      (node (ref "USB1") (pin "B1") (pinfunction "GND_B1") (pintype "passive"))
      (node (ref "USB1") (pin "B12") (pinfunction "GND_B12") (pintype "passive"))
      (node (ref "X1") (pin "2") (pinfunction "2_2") (pintype "passive"))
      (node (ref "X1") (pin "4") (pinfunction "4_4") (pintype "passive"))
    )
    (net (code "52") (name "KEY_POS1") (class "Default")
      (node (ref "1") (pin "11") (pinfunction "11_11") (pintype "passive"))
      (node (ref "U1") (pin "8") (pinfunction "PC0_8") (pintype "passive"))
    )
    (net (code "53") (name "KEY_POS2") (class "Default")
      (node (ref "1") (pin "12") (pinfunction "12_12") (pintype "passive"))
      (node (ref "U1") (pin "9") (pinfunction "PC1_9") (pintype "passive"))
    )
    (net (code "54") (name "KEY_POS3") (class "Default")
      (node (ref "1") (pin "13") (pinfunction "13_13") (pintype "passive"))
      (node (ref "U1") (pin "10") (pinfunction "PC2_10") (pintype "passive"))
    )
    (net (code "55") (name "KEY_POS4") (class "Default")
      (node (ref "1") (pin "14") (pinfunction "14_14") (pintype "passive"))
      (node (ref "U1") (pin "11") (pinfunction "PC3_11") (pintype "passive"))
    )
    (net (code "56") (name "KEY_POS5") (class "Default")
      (node (ref "1") (pin "15") (pinfunction "15_15") (pintype "passive"))
      (node (ref "U1") (pin "24") (pinfunction "PC4_24") (pintype "passive"))
    )
    (net (code "57") (name "KEY_POS6") (class "Default")
      (node (ref "1") (pin "16") (pinfunction "16_16") (pintype "passive"))
      (node (ref "U1") (pin "25") (pinfunction "PC5_25") (pintype "passive"))
    )
    (net (code "58") (name "KEY_POS7") (class "Default")
      (node (ref "1") (pin "17") (pinfunction "17_17") (pintype "passive"))
      (node (ref "U1") (pin "37") (pinfunction "PC6_37") (pintype "passive"))
    )
    (net (code "59") (name "KEY_POS8") (class "Default")
      (node (ref "1") (pin "18") (pinfunction "18_18") (pintype "passive"))
      (node (ref "U1") (pin "38") (pinfunction "PC7_38") (pintype "passive"))
    )
    (net (code "60") (name "KEY_POS9") (class "Default")
      (node (ref "1") (pin "19") (pinfunction "19_19") (pintype "passive"))
      (node (ref "U1") (pin "39") (pinfunction "PC8_39") (pintype "passive"))
    )
    (net (code "61") (name "KEY_POS10") (class "Default")
      (node (ref "1") (pin "20") (pinfunction "20_20") (pintype "passive"))
      (node (ref "U1") (pin "53") (pinfunction "PC12_53") (pintype "passive"))
    )
    (net (code "62") (name "KEY_POS11") (class "Default")
      (node (ref "1") (pin "21") (pinfunction "21_21") (pintype "passive"))
      (node (ref "U1") (pin "54") (pinfunction "PD2_54") (pintype "passive"))
    )
    (net (code "63") (name "KEY_POS12") (class "Default")
      (node (ref "1") (pin "22") (pinfunction "22_22") (pintype "passive"))
      (node (ref "U1") (pin "2") (pinfunction "PC13_2") (pintype "passive"))
    )
    (net (code "64") (name "KEY_POS13") (class "Default")
      (node (ref "1") (pin "23") (pinfunction "23_23") (pintype "passive"))
      (node (ref "U1") (pin "3") (pinfunction "OSC32_IN/PC14_3") (pintype "passive"))
    )
    (net (code "65") (name "KEY_POS14") (class "Default")
      (node (ref "1") (pin "24") (pinfunction "24_24") (pintype "passive"))
      (node (ref "U1") (pin "4") (pinfunction "OSC32_OUT/PC15_4") (pintype "passive"))
    )
    (net (code "66") (name "KEY_SEG1") (class "Default")
      (node (ref "1") (pin "31") (pinfunction "31_31") (pintype "passive"))
      (node (ref "U1") (pin "27") (pinfunction "PB1_27") (pintype "passive"))
    )
    (net (code "67") (name "KEY_SEG2") (class "Default")
      (node (ref "1") (pin "30") (pinfunction "30_30") (pintype "passive"))
      (node (ref "U1") (pin "29") (pinfunction "PB10_29") (pintype "passive"))
    )
    (net (code "68") (name "KEY_SEG3") (class "Default")
      (node (ref "1") (pin "29") (pinfunction "29_29") (pintype "passive"))
      (node (ref "U1") (pin "30") (pinfunction "PB11_30") (pintype "passive"))
    )
    (net (code "69") (name "KEY_SEG4") (class "Default")
      (node (ref "1") (pin "28") (pinfunction "28_28") (pintype "passive"))
      (node (ref "U1") (pin "33") (pinfunction "PB12_33") (pintype "passive"))
    )
    (net (code "70") (name "KEY_SEG5") (class "Default")
      (node (ref "1") (pin "27") (pinfunction "27_27") (pintype "passive"))
      (node (ref "U1") (pin "34") (pinfunction "PB13_34") (pintype "passive"))
    )
    (net (code "71") (name "KEY_SEG6") (class "Default")
      (node (ref "1") (pin "26") (pinfunction "26_26") (pintype "passive"))
      (node (ref "U1") (pin "35") (pinfunction "PB14_35") (pintype "passive"))
    )
    (net (code "72") (name "Net-(1-Pad35)") (class "Default")
      (node (ref "1") (pin "35") (pinfunction "35_35") (pintype "passive"))
      (node (ref "R1") (pin "5") (pinfunction "5_5") (pintype "passive"))
    )
    (net (code "73") (name "Net-(1-Pad36)") (class "Default")
      (node (ref "1") (pin "36") (pinfunction "36_36") (pintype "passive"))
      (node (ref "R1") (pin "6") (pinfunction "6_6") (pintype "passive"))
    )
    (net (code "74") (name "Net-(1-Pad37)") (class "Default")
      (node (ref "1") (pin "37") (pinfunction "37_37") (pintype "passive"))
      (node (ref "R1") (pin "7") (pinfunction "7_7") (pintype "passive"))
    )
    (net (code "75") (name "Net-(1-Pad38)") (class "Default")
      (node (ref "1") (pin "38") (pinfunction "38_38") (pintype "passive"))
      (node (ref "R1") (pin "8") (pinfunction "8_8") (pintype "passive"))
    )
    (net (code "76") (name "Net-(D1-A)") (class "Default")
      (node (ref "1") (pin "9") (pinfunction "9_9") (pintype "passive"))
      (node (ref "C8") (pin "2") (pinfunction "2_2") (pintype "passive"))
      (node (ref "D1") (pin "1") (pinfunction "A_1") (pintype "passive"))
      (node (ref "R9") (pin "8") (pinfunction "8_8") (pintype "passive"))
    )
    (net (code "77") (name "Net-(D2-A)") (class "Default")
      (node (ref "1") (pin "8") (pinfunction "8_8") (pintype "passive"))
      (node (ref "C9") (pin "2") (pinfunction "2_2") (pintype "passive"))
      (node (ref "D2") (pin "1") (pinfunction "A_1") (pintype "passive"))
      (node (ref "R9") (pin "7") (pinfunction "7_7") (pintype "passive"))
    )
    (net (code "78") (name "Net-(D3-A)") (class "Default")
      (node (ref "1") (pin "7") (pinfunction "7_7") (pintype "passive"))
      (node (ref "C10") (pin "2") (pinfunction "2_2") (pintype "passive"))
      (node (ref "D3") (pin "1") (pinfunction "A_1") (pintype "passive"))
      (node (ref "R9") (pin "6") (pinfunction "6_6") (pintype "passive"))
    )
    (net (code "79") (name "Net-(F1-Pad2)") (class "Default")
      (node (ref "F1") (pin "2") (pinfunction "2_2") (pintype "passive"))
      (node (ref "P1") (pin "4") (pinfunction "4_4") (pintype "passive"))
    )
    (net (code "80") (name "Net-(IC1-BST)") (class "Default")
      (node (ref "C37") (pin "1") (pinfunction "1_1") (pintype "passive"))
      (node (ref "IC1") (pin "7") (pinfunction "BST_7") (pintype "passive"))
    )
    (net (code "81") (name "Net-(IC1-FLED{slash}BSET{slash}IDA2)") (class "Default")
      (node (ref "IC1") (pin "21") (pinfunction "FLED/BSET/IDA2_21") (pintype "passive"))
      (node (ref "LED1") (pin "2") (pinfunction "K_2") (pintype "passive"))
      (node (ref "R27") (pin "2") (pinfunction "2_2") (pintype "passive"))
    )
    (net (code "82") (name "Net-(IC1-KEY{slash}GSET{slash}IDA1)") (class "Default")
      (node (ref "IC1") (pin "20") (pinfunction "KEY/GSET/IDA1_20") (pintype "passive"))
      (node (ref "R25") (pin "2") (pinfunction "2_2") (pintype "passive"))
    )
    (net (code "83") (name "Net-(IC1-LED5{slash}CSET)") (class "Default")
      (node (ref "IC1") (pin "22") (pinfunction "LED5/CSET_22") (pintype "passive"))
      (node (ref "R20") (pin "1") (pinfunction "1_1") (pintype "passive"))
    )
    (net (code "84") (name "Net-(IC1-SW_1)") (class "Default")
      (node (ref "C37") (pin "2") (pinfunction "2_2") (pintype "passive"))
      (node (ref "IC1") (pin "2") (pinfunction "SW_1_2") (pintype "passive"))
      (node (ref "IC1") (pin "3") (pinfunction "SW_2_3") (pintype "passive"))
      (node (ref "IC1") (pin "4") (pinfunction "SW_3_4") (pintype "passive"))
      (node (ref "IC1") (pin "5") (pinfunction "SW_4_5") (pintype "passive"))
      (node (ref "IC1") (pin "6") (pinfunction "SW_5_6") (pintype "passive"))
      (node (ref "L1") (pin "2") (pinfunction "2_2") (pintype "passive"))
    )
    (net (code "85") (name "Net-(IC1-VOUTSN)") (class "Default")
      (node (ref "C26") (pin "1") (pinfunction "1_1") (pintype "passive"))
      (node (ref "C27") (pin "1") (pinfunction "1_1") (pintype "passive"))
      (node (ref "C28") (pin "1") (pinfunction "1_1") (pintype "passive"))
      (node (ref "C38") (pin "1") (pinfunction "1_1") (pintype "passive"))
      (node (ref "IC1") (pin "28") (pinfunction "VOUTSN_28") (pintype "passive"))
      (node (ref "IC1") (pin "29") (pinfunction "VOUT_1_29") (pintype "passive"))
      (node (ref "IC1") (pin "30") (pinfunction "VOUT_2_30") (pintype "passive"))
      (node (ref "IC1") (pin "31") (pinfunction "VOUT_3_31") (pintype "passive"))
      (node (ref "IC1") (pin "32") (pinfunction "VOUT_4_32") (pintype "passive"))
      (node (ref "IC1") (pin "33") (pinfunction "VOUT_5_33") (pintype "passive"))
      (node (ref "R13") (pin "1") (pinfunction "1_1") (pintype "passive"))
    )
    (net (code "86") (name "Net-(IC3-CS)") (class "Default")
      (node (ref "IC3") (pin "2") (pinfunction "CS_2") (pintype "passive"))
      (node (ref "R21") (pin "1") (pinfunction "1_1") (pintype "passive"))
    )
    (net (code "87") (name "Net-(IC3-OC)") (class "Default")
      (node (ref "IC3") (pin "3") (pinfunction "OC_3") (pintype "passive"))
      (node (ref "Q4") (pin "4") (pinfunction "4_4") (pintype "passive"))
    )
    (net (code "88") (name "Net-(IC3-OD)") (class "Default")
      (node (ref "IC3") (pin "1") (pinfunction "OD_1") (pintype "passive"))
      (node (ref "Q3") (pin "4") (pinfunction "4_4") (pintype "passive"))
    )
    (net (code "89") (name "Net-(IC3-VCC)") (class "Default")
      (node (ref "C48") (pin "1") (pinfunction "1_1") (pintype "passive"))
      (node (ref "IC3") (pin "5") (pinfunction "VCC_5") (pintype "passive"))
      (node (ref "R19") (pin "1") (pinfunction "1_1") (pintype "passive"))
    )
    (net (code "90") (name "Net-(IC4-SENSE)") (class "Default")
      (node (ref "IC4") (pin "4") (pinfunction "SENSE_4") (pintype "passive"))
      (node (ref "R24") (pin "1") (pinfunction "1_1") (pintype "passive"))
    )
    (net (code "91") (name "Net-(IC4-~{SD})") (class "Default")
      (node (ref "IC4") (pin "1") (pinfunction "~{SD}_1") (pintype "passive"))
      (node (ref "R22") (pin "2") (pinfunction "2_2") (pintype "passive"))
      (node (ref "R23") (pin "2") (pinfunction "2_2") (pintype "passive"))
    )
    (net (code "92") (name "Net-(LED1-A)") (class "Default")
      (node (ref "LED1") (pin "1") (pinfunction "A_1") (pintype "passive"))
      (node (ref "R26") (pin "2") (pinfunction "2_2") (pintype "passive"))
    )
    (net (code "93") (name "Net-(P1-Pad1)") (class "Default")
      (node (ref "P1") (pin "1") (pinfunction "1_1") (pintype "passive"))
      (node (ref "R2") (pin "2") (pinfunction "2_2") (pintype "passive"))
    )
    (net (code "94") (name "Net-(P1-Pad2)") (class "Default")
      (node (ref "P1") (pin "2") (pinfunction "2_2") (pintype "passive"))
      (node (ref "R3") (pin "2") (pinfunction "2_2") (pintype "passive"))
    )
    (net (code "95") (name "Net-(Q1-B)") (class "Default")
      (node (ref "Q1") (pin "1") (pinfunction "B_1") (pintype "passive"))
      (node (ref "R4") (pin "2") (pinfunction "2_2") (pintype "passive"))
      (node (ref "R6") (pin "1") (pinfunction "1_1") (pintype "passive"))
    )
    (net (code "96") (name "Net-(Q1-C)") (class "Default")
      (node (ref "Q1") (pin "3") (pinfunction "C_3") (pintype "passive"))
      (node (ref "R7") (pin "2") (pinfunction "2_2") (pintype "passive"))
    )
    (net (code "97") (name "Net-(Q3-Pad5)") (class "Default")
      (node (ref "Q3") (pin "5") (pinfunction "5_5") (pintype "passive"))
      (node (ref "Q3") (pin "6") (pinfunction "6_6") (pintype "passive"))
      (node (ref "Q3") (pin "7") (pinfunction "7_7") (pintype "passive"))
      (node (ref "Q3") (pin "8") (pinfunction "8_8") (pintype "passive"))
      (node (ref "Q4") (pin "5") (pinfunction "5_5") (pintype "passive"))
      (node (ref "Q4") (pin "6") (pinfunction "6_6") (pintype "passive"))
      (node (ref "Q4") (pin "7") (pinfunction "7_7") (pintype "passive"))
      (node (ref "Q4") (pin "8") (pinfunction "8_8") (pintype "passive"))
    )
    (net (code "98") (name "Net-(Q5-B)") (class "Default")
      (node (ref "Q5") (pin "1") (pinfunction "B_1") (pintype "passive"))
      (node (ref "R28") (pin "2") (pinfunction "2_2") (pintype "passive"))
    )
    (net (code "99") (name "Net-(Q6-B)") (class "Default")
      (node (ref "Q6") (pin "1") (pinfunction "B_1") (pintype "passive"))
      (node (ref "R29") (pin "2") (pinfunction "2_2") (pintype "passive"))
    )
    (net (code "100") (name "Net-(R14-Pad2)") (class "Default")
      (node (ref "R14") (pin "2") (pinfunction "2_2") (pintype "passive"))
      (node (ref "R15") (pin "1") (pinfunction "1_1") (pintype "passive"))
      (node (ref "U3") (pin "3") (pinfunction "EN_3") (pintype "passive"))
    )
    (net (code "101") (name "Net-(U1-RCC_OSC_IN{slash}PH0)") (class "Default")
      (node (ref "C1") (pin "1") (pinfunction "1_1") (pintype "passive"))
      (node (ref "U1") (pin "5") (pinfunction "RCC_OSC_IN/PH0_5") (pintype "passive"))
      (node (ref "X1") (pin "3") (pinfunction "3_3") (pintype "passive"))
    )
    (net (code "102") (name "Net-(U1-RCC_OSC_OUT{slash}PH1)") (class "Default")
      (node (ref "C2") (pin "1") (pinfunction "1_1") (pintype "passive"))
      (node (ref "U1") (pin "6") (pinfunction "RCC_OSC_OUT/PH1_6") (pintype "passive"))
      (node (ref "X1") (pin "1") (pinfunction "1_1") (pintype "passive"))
    )
    (net (code "103") (name "Net-(U1-VCAP_1)") (class "Default")
      (node (ref "C14") (pin "2") (pinfunction "2_2") (pintype "passive"))
      (node (ref "U1") (pin "31") (pinfunction "VCAP_1_31") (pintype "passive"))
    )
    (net (code "104") (name "Net-(U1-VCAP_2)") (class "Default")
      (node (ref "C15") (pin "2") (pinfunction "2_2") (pintype "passive"))
      (node (ref "U1") (pin "47") (pinfunction "VCAP_2_47") (pintype "passive"))
    )
    (net (code "105") (name "USBVCC") (class "Default")
      (node (ref "C24") (pin "2") (pinfunction "2_2") (pintype "passive"))
      (node (ref "C25") (pin "2") (pinfunction "2_2") (pintype "passive"))
      (node (ref "IC1") (pin "12") (pinfunction "VBUSC_12") (pintype "passive"))
      (node (ref "Q2") (pin "1") (pinfunction "1_1") (pintype "passive"))
      (node (ref "Q2") (pin "2") (pinfunction "2_2") (pintype "passive"))
      (node (ref "Q2") (pin "3") (pinfunction "3_3") (pintype "passive"))
      (node (ref "USB1") (pin "A4") (pinfunction "VBUS_A4") (pintype "passive"))
      (node (ref "USB1") (pin "A9") (pinfunction "VBUS_A9") (pintype "passive"))
      (node (ref "USB1") (pin "B4") (pinfunction "VBUS_B4") (pintype "passive"))
      (node (ref "USB1") (pin "B9") (pinfunction "VBUS_B9") (pintype "passive"))
    )
    (net (code "106") (name "VCC3V3") (class "Default")
      (node (ref "C12") (pin "2") (pinfunction "2_2") (pintype "passive"))
      (node (ref "C13") (pin "2") (pinfunction "2_2") (pintype "passive"))
      (node (ref "C20") (pin "1") (pinfunction "1_1") (pintype "passive"))
      (node (ref "C21") (pin "1") (pinfunction "1_1") (pintype "passive"))
      (node (ref "C4") (pin "2") (pinfunction "2_2") (pintype "passive"))
      (node (ref "C43") (pin "2") (pinfunction "2_2") (pintype "passive"))
      (node (ref "C44") (pin "2") (pinfunction "2_2") (pintype "passive"))
      (node (ref "C5") (pin "2") (pinfunction "2_2") (pintype "passive"))
      (node (ref "C6") (pin "2") (pinfunction "2_2") (pintype "passive"))
      (node (ref "C7") (pin "2") (pinfunction "2_2") (pintype "passive"))
      (node (ref "F1") (pin "1") (pinfunction "1_1") (pintype "passive"))
      (node (ref "IC2") (pin "2") (pinfunction "3V3_2") (pintype "passive"))
      (node (ref "P4") (pin "1") (pinfunction "1_1") (pintype "passive"))
      (node (ref "R12") (pin "1") (pinfunction "1_1") (pintype "passive"))
      (node (ref "R16") (pin "1") (pinfunction "1_1") (pintype "passive"))
      (node (ref "R17") (pin "1") (pinfunction "1_1") (pintype "passive"))
      (node (ref "R8") (pin "2") (pinfunction "2_2") (pintype "passive"))
      (node (ref "U1") (pin "1") (pinfunction "VBAT_1") (pintype "passive"))
      (node (ref "U1") (pin "19") (pinfunction "VDD_19") (pintype "passive"))
      (node (ref "U1") (pin "32") (pinfunction "VDD_32") (pintype "passive"))
      (node (ref "U1") (pin "48") (pinfunction "VDD_48") (pintype "passive"))
      (node (ref "U1") (pin "64") (pinfunction "VDD_64") (pintype "passive"))
      (node (ref "U2") (pin "5") (pinfunction "VOUT_5") (pintype "passive"))
    )
    (net (code "107") (name "VCC3V3_1A") (class "Default")
      (node (ref "1") (pin "33") (pinfunction "33_33") (pintype "passive"))
      (node (ref "C51") (pin "1") (pinfunction "1_1") (pintype "passive"))
      (node (ref "C52") (pin "1") (pinfunction "1_1") (pintype "passive"))
      (node (ref "IC4") (pin "3") (pinfunction "OUT_3") (pintype "output"))
      (node (ref "P3") (pin "1") (pinfunction "1_1") (pintype "passive"))
      (node (ref "R24") (pin "2") (pinfunction "2_2") (pintype "passive"))
    )
    (net (code "108") (name "VCC_LCD") (class "Default")
      (node (ref "1") (pin "39") (pinfunction "39_39") (pintype "passive"))
      (node (ref "C41") (pin "1") (pinfunction "1_1") (pintype "passive"))
      (node (ref "C42") (pin "1") (pinfunction "1_1") (pintype "passive"))
      (node (ref "P2") (pin "1") (pinfunction "1_1") (pintype "passive"))
      (node (ref "P2") (pin "3") (pinfunction "3_3") (pintype "passive"))
      (node (ref "Q1") (pin "2") (pinfunction "E_2") (pintype "passive"))
      (node (ref "R6") (pin "2") (pinfunction "2_2") (pintype "passive"))
      (node (ref "U3") (pin "5") (pinfunction "VOUT_5") (pintype "passive"))
    )
    (net (code "109") (name "unconnected-(IC1-CCL{slash}WLED-Pad39)") (class "Default")
      (node (ref "IC1") (pin "39") (pinfunction "CCL/WLED_39") (pintype "passive+no_connect"))
    )
    (net (code "110") (name "unconnected-(IC1-DATA-Pad8)") (class "Default")
      (node (ref "IC1") (pin "8") (pinfunction "DATA_8") (pintype "passive+no_connect"))
    )
    (net (code "111") (name "unconnected-(IC1-DMA1-Pad46)") (class "Default")
      (node (ref "IC1") (pin "46") (pinfunction "DMA1_46") (pintype "passive+no_connect"))
    )
    (net (code "112") (name "unconnected-(IC1-DMA2-Pad48)") (class "Default")
      (node (ref "IC1") (pin "48") (pinfunction "DMA2_48") (pintype "passive+no_connect"))
    )
    (net (code "113") (name "unconnected-(IC1-DMB-Pad44)") (class "Default")
      (node (ref "IC1") (pin "44") (pinfunction "DMB_44") (pintype "passive+no_connect"))
    )
    (net (code "114") (name "unconnected-(IC1-DMC-Pad42)") (class "Default")
      (node (ref "IC1") (pin "42") (pinfunction "DMC_42") (pintype "passive+no_connect"))
    )
    (net (code "115") (name "unconnected-(IC1-DPA1-Pad47)") (class "Default")
      (node (ref "IC1") (pin "47") (pinfunction "DPA1_47") (pintype "passive+no_connect"))
    )
    (net (code "116") (name "unconnected-(IC1-DPA2-Pad1)") (class "Default")
      (node (ref "IC1") (pin "1") (pinfunction "DPA2_1") (pintype "passive+no_connect"))
    )
    (net (code "117") (name "unconnected-(IC1-DPB-Pad45)") (class "Default")
      (node (ref "IC1") (pin "45") (pinfunction "DPB_45") (pintype "passive+no_connect"))
    )
    (net (code "118") (name "unconnected-(IC1-DPC-Pad43)") (class "Default")
      (node (ref "IC1") (pin "43") (pinfunction "DPC_43") (pintype "passive+no_connect"))
    )
    (net (code "119") (name "unconnected-(IC1-GATEA1-Pad36)") (class "Default")
      (node (ref "IC1") (pin "36") (pinfunction "GATEA1_36") (pintype "passive+no_connect"))
    )
    (net (code "120") (name "unconnected-(IC1-GATEA2-Pad35)") (class "Default")
      (node (ref "IC1") (pin "35") (pinfunction "GATEA2_35") (pintype "passive+no_connect"))
    )
    (net (code "121") (name "unconnected-(IC1-GATEB-Pad37)") (class "Default")
      (node (ref "IC1") (pin "37") (pinfunction "GATEB_37") (pintype "passive+no_connect"))
    )
    (net (code "122") (name "unconnected-(IC1-GATEL-Pad34)") (class "Default")
      (node (ref "IC1") (pin "34") (pinfunction "GATEL_34") (pintype "passive+no_connect"))
    )
    (net (code "123") (name "unconnected-(IC1-VBUSA1-Pad10)") (class "Default")
      (node (ref "IC1") (pin "10") (pinfunction "VBUSA1_10") (pintype "passive+no_connect"))
    )
    (net (code "124") (name "unconnected-(IC1-VBUSA2-Pad15)") (class "Default")
      (node (ref "IC1") (pin "15") (pinfunction "VBUSA2_15") (pintype "passive+no_connect"))
    )
    (net (code "125") (name "unconnected-(IC1-VBUSB-Pad11)") (class "Default")
      (node (ref "IC1") (pin "11") (pinfunction "VBUSB_11") (pintype "passive+no_connect"))
    )
    (net (code "126") (name "unconnected-(IC1-VBUSL-Pad16)") (class "Default")
      (node (ref "IC1") (pin "16") (pinfunction "VBUSL_16") (pintype "passive+no_connect"))
    )
    (net (code "127") (name "unconnected-(IC1-VOUTA1-Pad9)") (class "Default")
      (node (ref "IC1") (pin "9") (pinfunction "VOUTA1_9") (pintype "passive+no_connect"))
    )
    (net (code "128") (name "unconnected-(IC1-VOUTA2-Pad14)") (class "Default")
      (node (ref "IC1") (pin "14") (pinfunction "VOUTA2_14") (pintype "passive+no_connect"))
    )
    (net (code "129") (name "unconnected-(IC2-IO1-Pad39)") (class "Default")
      (node (ref "IC2") (pin "39") (pinfunction "IO1_39") (pintype "passive+no_connect"))
    )
    (net (code "130") (name "unconnected-(IC2-IO2-Pad38)") (class "Default")
      (node (ref "IC2") (pin "38") (pinfunction "IO2_38") (pintype "passive+no_connect"))
    )
    (net (code "131") (name "unconnected-(IC2-IO3-Pad15)") (class "Default")
      (node (ref "IC2") (pin "15") (pinfunction "IO3_15") (pintype "passive+no_connect"))
    )
    (net (code "132") (name "unconnected-(IC2-IO4-Pad4)") (class "Default")
      (node (ref "IC2") (pin "4") (pinfunction "IO4_4") (pintype "passive+no_connect"))
    )
    (net (code "133") (name "unconnected-(IC2-IO5-Pad5)") (class "Default")
      (node (ref "IC2") (pin "5") (pinfunction "IO5_5") (pintype "passive+no_connect"))
    )
    (net (code "134") (name "unconnected-(IC2-IO6-Pad6)") (class "Default")
      (node (ref "IC2") (pin "6") (pinfunction "IO6_6") (pintype "passive+no_connect"))
    )
    (net (code "135") (name "unconnected-(IC2-IO7-Pad7)") (class "Default")
      (node (ref "IC2") (pin "7") (pinfunction "IO7_7") (pintype "passive+no_connect"))
    )
    (net (code "136") (name "unconnected-(IC2-IO8-Pad12)") (class "Default")
      (node (ref "IC2") (pin "12") (pinfunction "IO8_12") (pintype "passive+no_connect"))
    )
    (net (code "137") (name "unconnected-(IC2-IO9-Pad17)") (class "Default")
      (node (ref "IC2") (pin "17") (pinfunction "IO9_17") (pintype "passive+no_connect"))
    )
    (net (code "138") (name "unconnected-(IC2-IO10-Pad18)") (class "Default")
      (node (ref "IC2") (pin "18") (pinfunction "IO10_18") (pintype "passive+no_connect"))
    )
    (net (code "139") (name "unconnected-(IC2-IO11-Pad19)") (class "Default")
      (node (ref "IC2") (pin "19") (pinfunction "IO11_19") (pintype "passive+no_connect"))
    )
    (net (code "140") (name "unconnected-(IC2-IO12-Pad20)") (class "Default")
      (node (ref "IC2") (pin "20") (pinfunction "IO12_20") (pintype "passive+no_connect"))
    )
    (net (code "141") (name "unconnected-(IC2-IO13-Pad21)") (class "Default")
      (node (ref "IC2") (pin "21") (pinfunction "IO13_21") (pintype "passive+no_connect"))
    )
    (net (code "142") (name "unconnected-(IC2-IO14-Pad22)") (class "Default")
      (node (ref "IC2") (pin "22") (pinfunction "IO14_22") (pintype "passive+no_connect"))
    )
    (net (code "143") (name "unconnected-(IC2-IO15-Pad8)") (class "Default")
      (node (ref "IC2") (pin "8") (pinfunction "IO15_8") (pintype "passive+no_connect"))
    )
    (net (code "144") (name "unconnected-(IC2-IO16-Pad9)") (class "Default")
      (node (ref "IC2") (pin "9") (pinfunction "IO16_9") (pintype "passive+no_connect"))
    )
    (net (code "145") (name "unconnected-(IC2-IO19-Pad13)") (class "Default")
      (node (ref "IC2") (pin "13") (pinfunction "IO19_13") (pintype "passive+no_connect"))
    )
    (net (code "146") (name "unconnected-(IC2-IO20-Pad14)") (class "Default")
      (node (ref "IC2") (pin "14") (pinfunction "IO20_14") (pintype "passive+no_connect"))
    )
    (net (code "147") (name "unconnected-(IC2-IO21-Pad23)") (class "Default")
      (node (ref "IC2") (pin "23") (pinfunction "IO21_23") (pintype "passive+no_connect"))
    )
    (net (code "148") (name "unconnected-(IC2-IO35-Pad28)") (class "Default")
      (node (ref "IC2") (pin "28") (pinfunction "IO35_28") (pintype "passive+no_connect"))
    )
    (net (code "149") (name "unconnected-(IC2-IO36-Pad29)") (class "Default")
      (node (ref "IC2") (pin "29") (pinfunction "IO36_29") (pintype "passive+no_connect"))
    )
    (net (code "150") (name "unconnected-(IC2-IO37-Pad30)") (class "Default")
      (node (ref "IC2") (pin "30") (pinfunction "IO37_30") (pintype "passive+no_connect"))
    )
    (net (code "151") (name "unconnected-(IC2-IO38-Pad31)") (class "Default")
      (node (ref "IC2") (pin "31") (pinfunction "IO38_31") (pintype "passive+no_connect"))
    )
    (net (code "152") (name "unconnected-(IC2-IO39-Pad32)") (class "Default")
      (node (ref "IC2") (pin "32") (pinfunction "IO39_32") (pintype "passive+no_connect"))
    )
    (net (code "153") (name "unconnected-(IC2-IO40-Pad33)") (class "Default")
      (node (ref "IC2") (pin "33") (pinfunction "IO40_33") (pintype "passive+no_connect"))
    )
    (net (code "154") (name "unconnected-(IC2-IO41-Pad34)") (class "Default")
      (node (ref "IC2") (pin "34") (pinfunction "IO41_34") (pintype "passive+no_connect"))
    )
    (net (code "155") (name "unconnected-(IC2-IO42-Pad35)") (class "Default")
      (node (ref "IC2") (pin "35") (pinfunction "IO42_35") (pintype "passive+no_connect"))
    )
    (net (code "156") (name "unconnected-(IC2-IO45-Pad26)") (class "Default")
      (node (ref "IC2") (pin "26") (pinfunction "IO45_26") (pintype "passive+no_connect"))
    )
    (net (code "157") (name "unconnected-(IC2-IO46-Pad16)") (class "Default")
      (node (ref "IC2") (pin "16") (pinfunction "IO46_16") (pintype "passive+no_connect"))
    )
    (net (code "158") (name "unconnected-(IC2-IO47-Pad24)") (class "Default")
      (node (ref "IC2") (pin "24") (pinfunction "IO47_24") (pintype "passive+no_connect"))
    )
    (net (code "159") (name "unconnected-(IC2-IO48-Pad25)") (class "Default")
      (node (ref "IC2") (pin "25") (pinfunction "IO48_25") (pintype "passive+no_connect"))
    )
    (net (code "160") (name "unconnected-(IC3-TD-Pad4)") (class "Default")
      (node (ref "IC3") (pin "4") (pinfunction "TD_4") (pintype "passive+no_connect"))
    )
    (net (code "161") (name "unconnected-(P1-PadMP1)") (class "Default")
      (node (ref "P1") (pin "MP1") (pinfunction "MP1_MP1") (pintype "passive+no_connect"))
    )
    (net (code "162") (name "unconnected-(P1-PadMP2)") (class "Default")
      (node (ref "P1") (pin "MP2") (pinfunction "MP2_MP2") (pintype "passive+no_connect"))
    )
    (net (code "163") (name "unconnected-(P2-PadMP1)") (class "Default")
      (node (ref "P2") (pin "MP1") (pinfunction "MP1_MP1") (pintype "passive+no_connect"))
    )
    (net (code "164") (name "unconnected-(P2-PadMP2)") (class "Default")
      (node (ref "P2") (pin "MP2") (pinfunction "MP2_MP2") (pintype "passive+no_connect"))
    )
    (net (code "165") (name "unconnected-(P3-PadMP1)") (class "Default")
      (node (ref "P3") (pin "MP1") (pinfunction "MP1_MP1") (pintype "passive+no_connect"))
    )
    (net (code "166") (name "unconnected-(P3-PadMP2)") (class "Default")
      (node (ref "P3") (pin "MP2") (pinfunction "MP2_MP2") (pintype "passive+no_connect"))
    )
    (net (code "167") (name "unconnected-(P4-PadMP1)") (class "Default")
      (node (ref "P4") (pin "MP1") (pinfunction "MP1_MP1") (pintype "passive+no_connect"))
    )
    (net (code "168") (name "unconnected-(P4-PadMP2)") (class "Default")
      (node (ref "P4") (pin "MP2") (pinfunction "MP2_MP2") (pintype "passive+no_connect"))
    )
    (net (code "169") (name "unconnected-(U2-NC-Pad4)") (class "Default")
      (node (ref "U2") (pin "4") (pinfunction "NC_4") (pintype "passive+no_connect"))
    )
    (net (code "170") (name "unconnected-(U3-NC-Pad4)") (class "Default")
      (node (ref "U3") (pin "4") (pinfunction "NC_4") (pintype "passive+no_connect"))
    )
    (net (code "171") (name "unconnected-(USB1-RX1+-PadB11)") (class "Default")
      (node (ref "USB1") (pin "B11") (pinfunction "RX1+_B11") (pintype "passive+no_connect"))
    )
    (net (code "172") (name "unconnected-(USB1-RX1--PadB10)") (class "Default")
      (node (ref "USB1") (pin "B10") (pinfunction "RX1-_B10") (pintype "passive+no_connect"))
    )
    (net (code "173") (name "unconnected-(USB1-RX2+-PadA11)") (class "Default")
      (node (ref "USB1") (pin "A11") (pinfunction "RX2+_A11") (pintype "passive+no_connect"))
    )
    (net (code "174") (name "unconnected-(USB1-RX2--PadA10)") (class "Default")
      (node (ref "USB1") (pin "A10") (pinfunction "RX2-_A10") (pintype "passive+no_connect"))
    )
    (net (code "175") (name "unconnected-(USB1-SBU1-PadA8)") (class "Default")
      (node (ref "USB1") (pin "A8") (pinfunction "SBU1_A8") (pintype "passive+no_connect"))
    )
    (net (code "176") (name "unconnected-(USB1-SBU2-PadB8)") (class "Default")
      (node (ref "USB1") (pin "B8") (pinfunction "SBU2_B8") (pintype "passive+no_connect"))
    )
    (net (code "177") (name "unconnected-(USB1-SH1-Pad1)") (class "Default")
      (node (ref "USB1") (pin "1") (pinfunction "SH1_1") (pintype "passive+no_connect"))
    )
    (net (code "178") (name "unconnected-(USB1-SH2-Pad2)") (class "Default")
      (node (ref "USB1") (pin "2") (pinfunction "SH2_2") (pintype "passive+no_connect"))
    )
    (net (code "179") (name "unconnected-(USB1-SH3-Pad3)") (class "Default")
      (node (ref "USB1") (pin "3") (pinfunction "SH3_3") (pintype "passive+no_connect"))
    )
    (net (code "180") (name "unconnected-(USB1-SH4-Pad4)") (class "Default")
      (node (ref "USB1") (pin "4") (pinfunction "SH4_4") (pintype "passive+no_connect"))
    )
    (net (code "181") (name "unconnected-(USB1-TX1+-PadA2)") (class "Default")
      (node (ref "USB1") (pin "A2") (pinfunction "TX1+_A2") (pintype "passive+no_connect"))
    )
    (net (code "182") (name "unconnected-(USB1-TX1--PadA3)") (class "Default")
      (node (ref "USB1") (pin "A3") (pinfunction "TX1-_A3") (pintype "passive+no_connect"))
    )
    (net (code "183") (name "unconnected-(USB1-TX2+-PadB2)") (class "Default")
      (node (ref "USB1") (pin "B2") (pinfunction "TX2+_B2") (pintype "passive+no_connect"))
    )
    (net (code "184") (name "unconnected-(USB1-TX2--PadB3)") (class "Default")
      (node (ref "USB1") (pin "B3") (pinfunction "TX2-_B3") (pintype "passive+no_connect"))
    )
  )
)
